# undercarriage.net
KiCad netlist of a schematic drawn in EAGLE
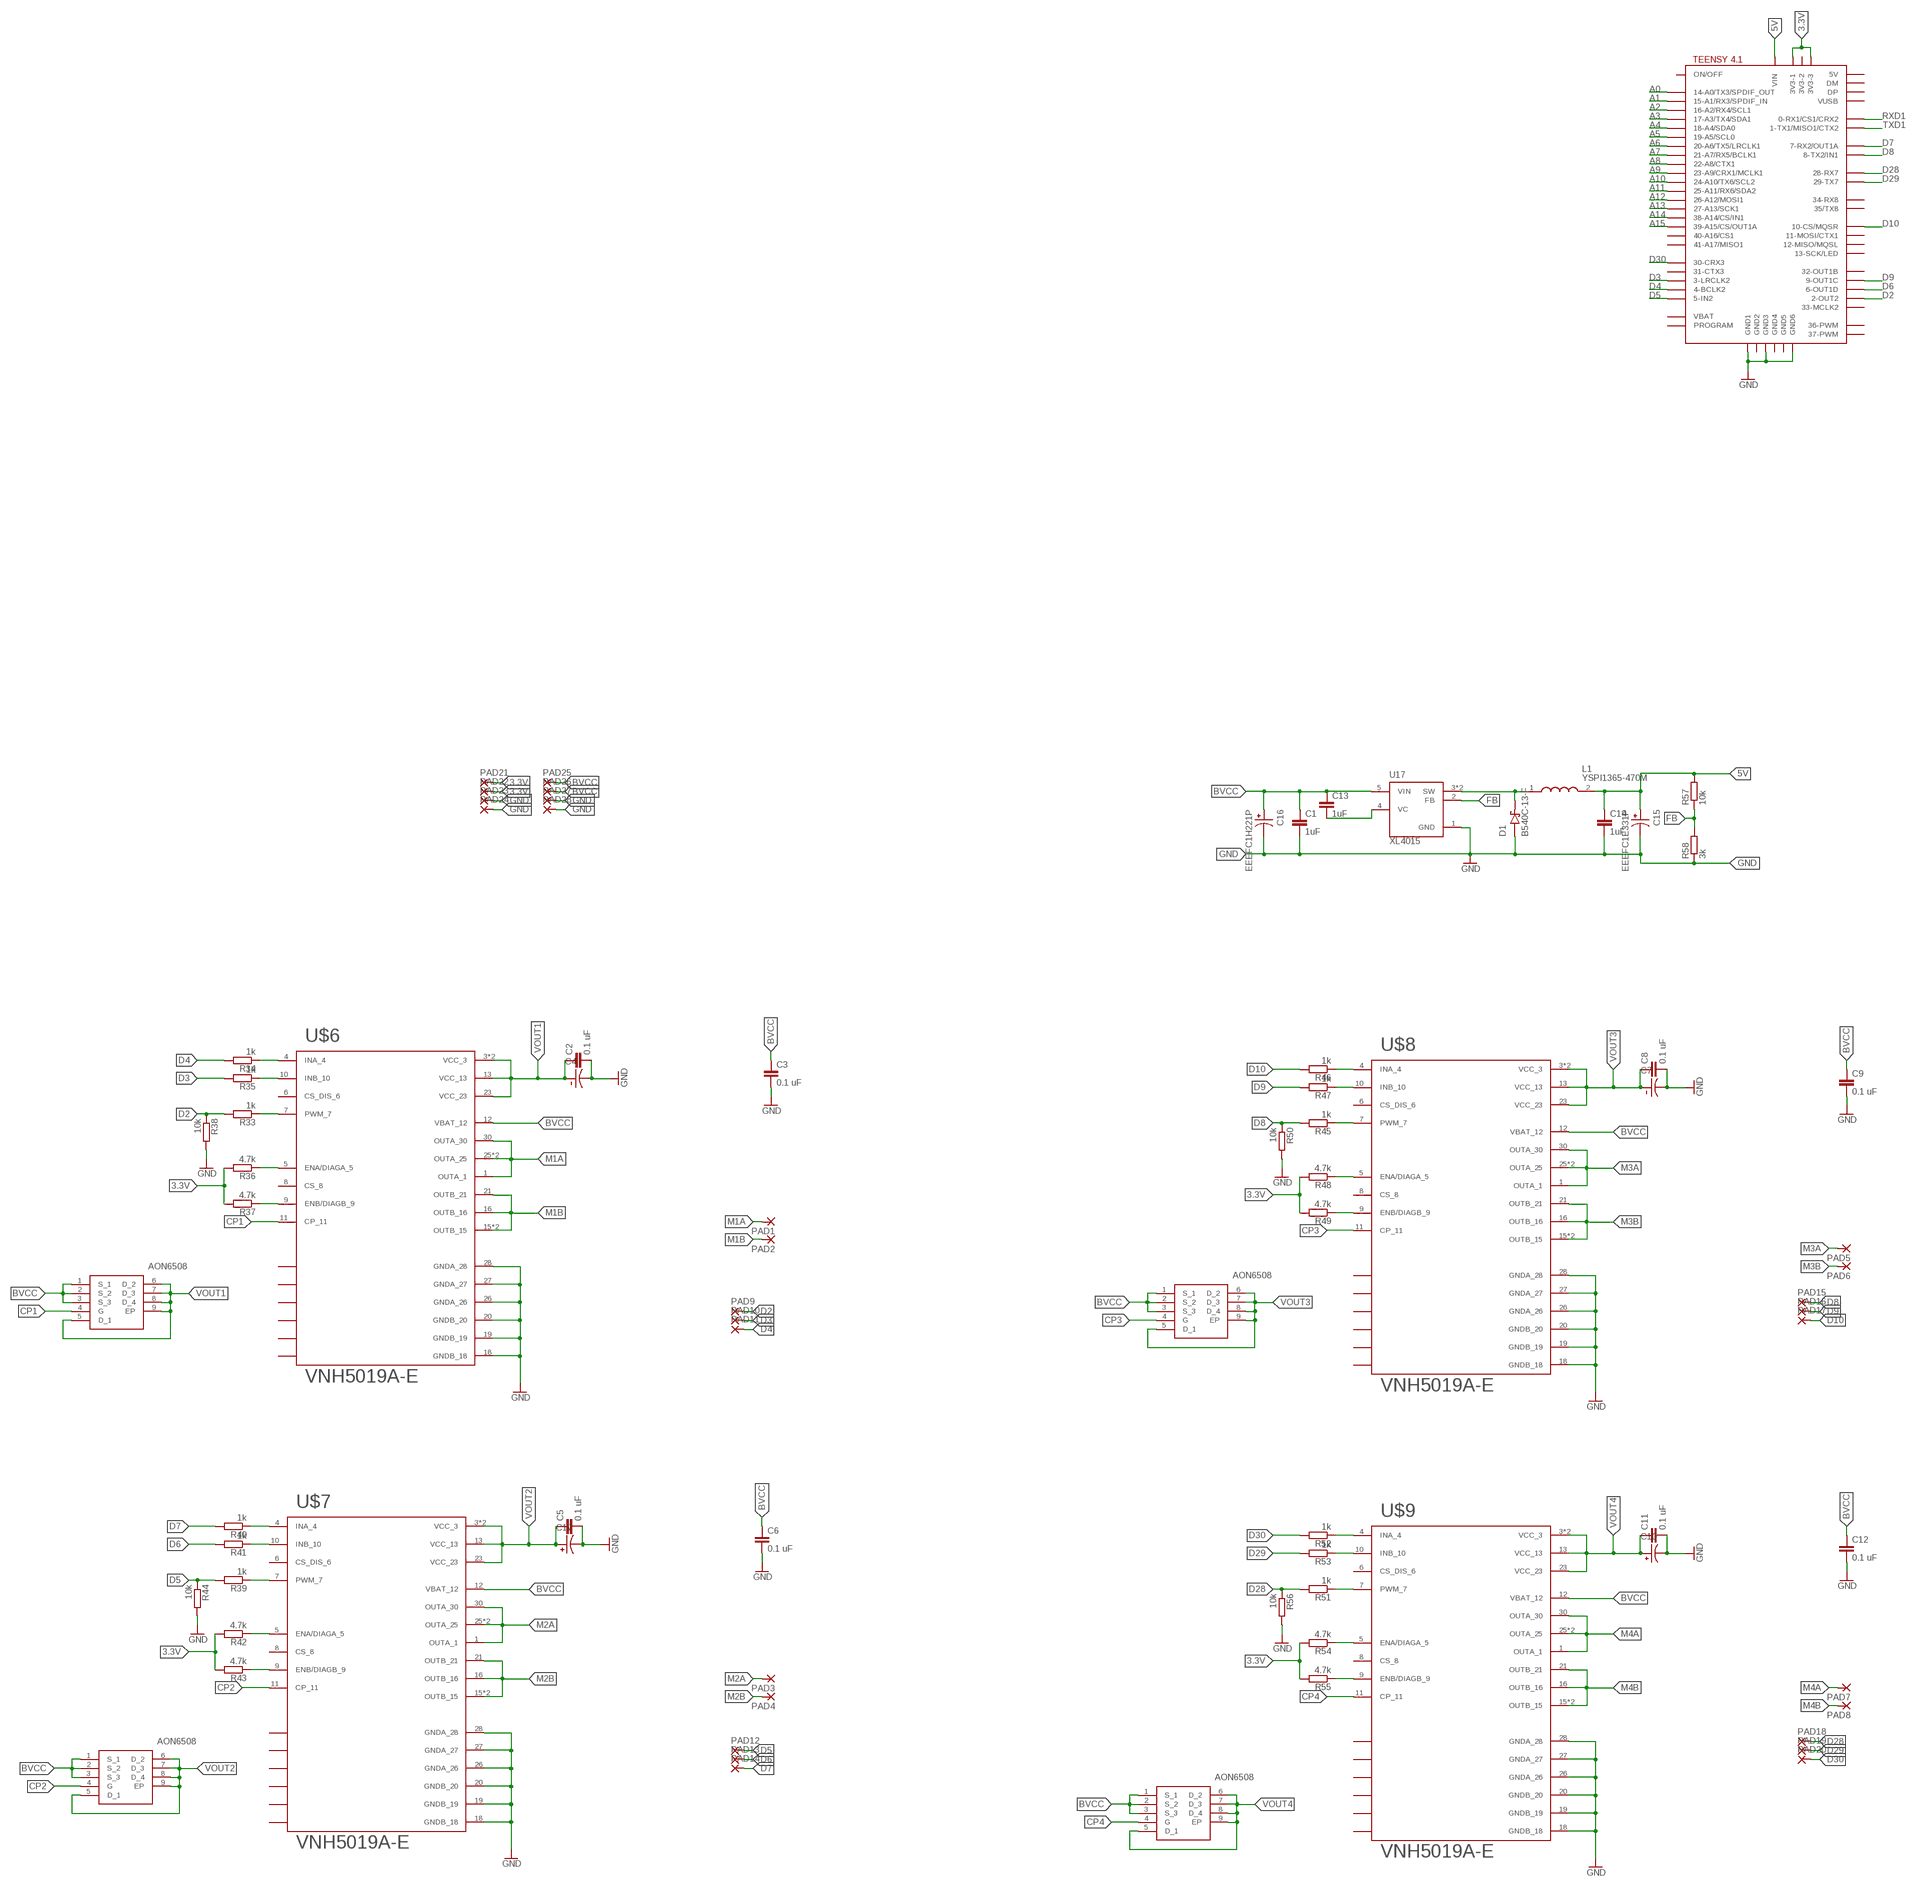
[diagram p0: schematic, sheet 1, part 1 of 2]
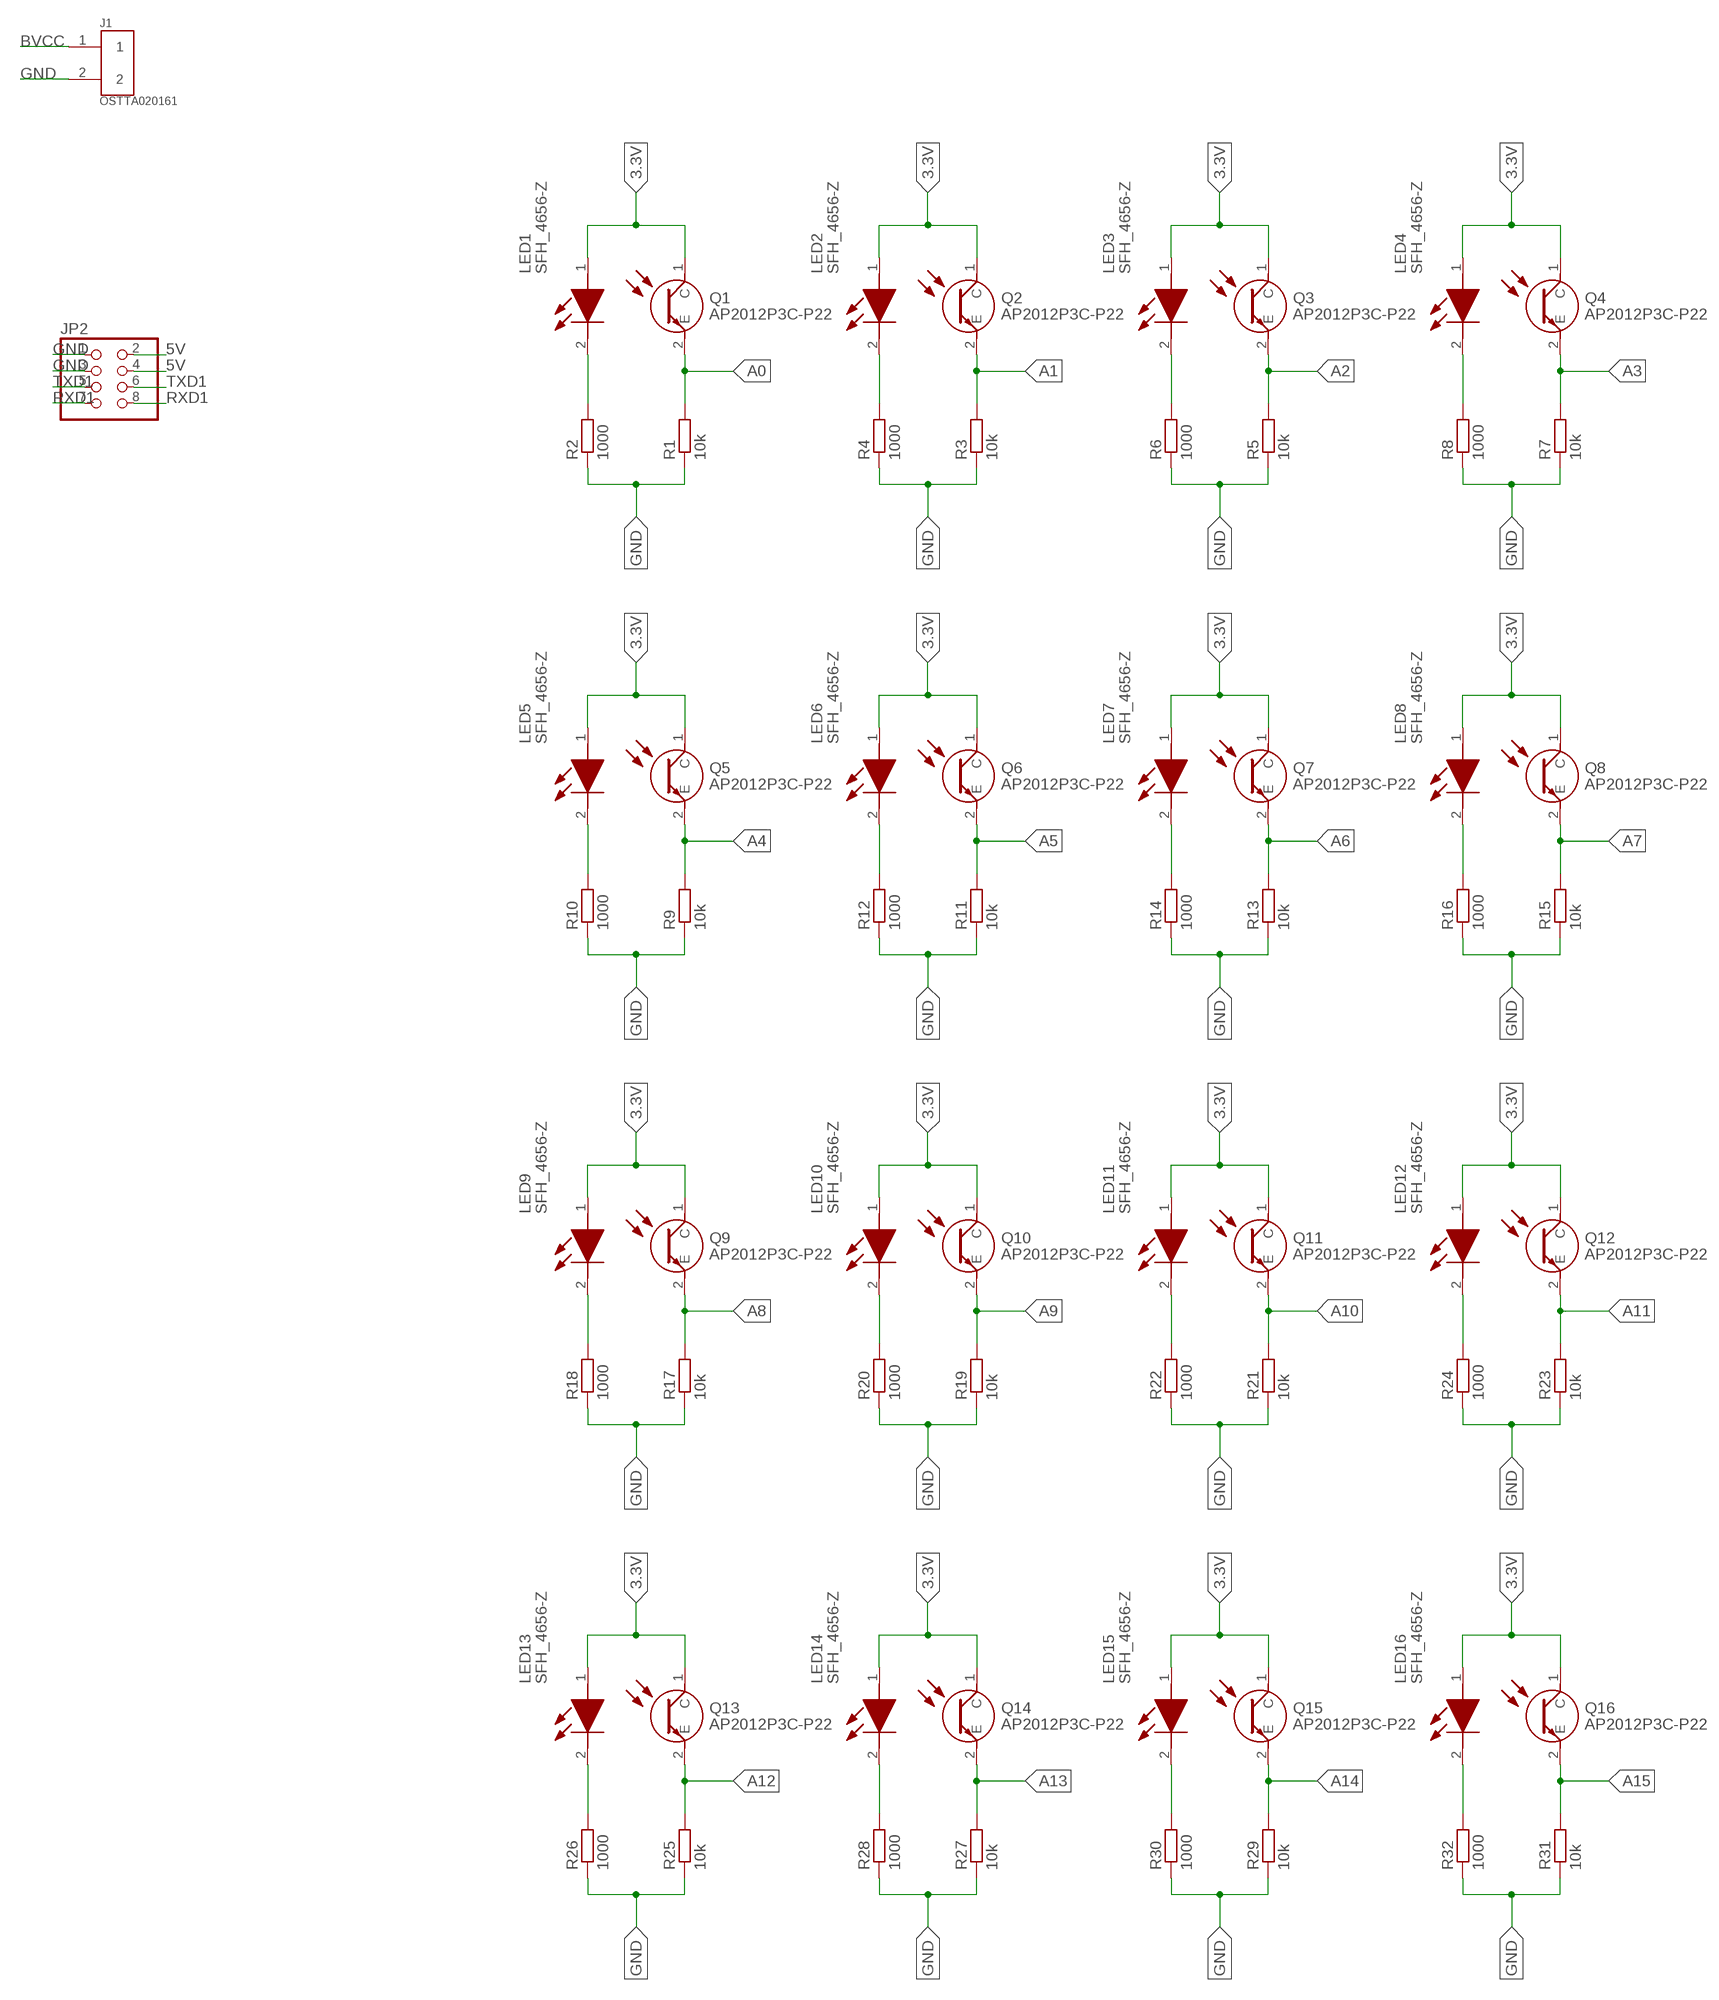
[diagram p1: schematic, sheet 1, part 2 of 2]

(export (version "E")
  (design (tool "Eeschema 10.0.6"))
  (components
    (comp (ref "C1")
      (value "1uF")
      (footprint "eagle-import:C0603")
      (libsource (lib "eagle-import") (part "C-EUC0603"))
    )
    (comp (ref "C2")
      (value "0.1 uF")
      (footprint "eagle-import:C0603")
      (libsource (lib "eagle-import") (part "C-EUC0603"))
    )
    (comp (ref "C3")
      (value "0.1 uF")
      (footprint "eagle-import:C0603")
      (libsource (lib "eagle-import") (part "C-EUC0603"))
    )
    (comp (ref "C4")
      (value "EEEFT1H470AP")
      (footprint "eagle-import:CAP_EEEFT1H470AP")
      (fields (field (name "MF") "Panasonic"))
      (libsource (lib "eagle-import") (part "EEEFT1H470AP"))
    )
    (comp (ref "C5")
      (value "0.1 uF")
      (footprint "eagle-import:C0603")
      (libsource (lib "eagle-import") (part "C-EUC0603"))
    )
    (comp (ref "C6")
      (value "0.1 uF")
      (footprint "eagle-import:C0603")
      (libsource (lib "eagle-import") (part "C-EUC0603"))
    )
    (comp (ref "C7")
      (value "EEEFT1H470AP")
      (footprint "eagle-import:CAP_EEEFT1H470AP")
      (fields (field (name "MF") "Panasonic"))
      (libsource (lib "eagle-import") (part "EEEFT1H470AP"))
    )
    (comp (ref "C8")
      (value "0.1 uF")
      (footprint "eagle-import:C0603")
      (libsource (lib "eagle-import") (part "C-EUC0603"))
    )
    (comp (ref "C9")
      (value "0.1 uF")
      (footprint "eagle-import:C0603")
      (libsource (lib "eagle-import") (part "C-EUC0603"))
    )
    (comp (ref "C10")
      (value "EEEFT1H470AP")
      (footprint "eagle-import:CAP_EEEFT1H470AP")
      (fields (field (name "MF") "Panasonic"))
      (libsource (lib "eagle-import") (part "EEEFT1H470AP"))
    )
    (comp (ref "C11")
      (value "0.1 uF")
      (footprint "eagle-import:C0603")
      (libsource (lib "eagle-import") (part "C-EUC0603"))
    )
    (comp (ref "C12")
      (value "0.1 uF")
      (footprint "eagle-import:C0603")
      (libsource (lib "eagle-import") (part "C-EUC0603"))
    )
    (comp (ref "C13")
      (value "1uF")
      (footprint "eagle-import:C0603")
      (libsource (lib "eagle-import") (part "C-EUC0603"))
    )
    (comp (ref "C14")
      (value "1uF")
      (footprint "eagle-import:C0603")
      (libsource (lib "eagle-import") (part "C-EUC0603"))
    )
    (comp (ref "C15")
      (value "EEEFC1E331P")
      (footprint "eagle-import:CAP_EEEFC1E331P")
      (fields (field (name "MF") "Panasonic"))
      (libsource (lib "eagle-import") (part "EEEFC1E331P"))
    )
    (comp (ref "C16")
      (value "EEEFC1H221P")
      (footprint "eagle-import:CAP_EEEFC1H221P")
      (fields (field (name "MF") "Panasonic"))
      (libsource (lib "eagle-import") (part "EEEFC1H221P"))
    )
    (comp (ref "C17")
      (value "EEEFT1H470AP")
      (footprint "eagle-import:CAP_EEEFT1H470AP")
      (fields (field (name "MF") "Panasonic"))
      (libsource (lib "eagle-import") (part "EEEFT1H470AP"))
    )
    (comp (ref "D1")
      (value "B540C-13-F")
      (footprint "eagle-import:DIOM6959X245N")
      (fields (field (name "MF") "Diodes Inc."))
      (libsource (lib "eagle-import") (part "B540C-13-F"))
    )
    (comp (ref "J1")
      (value "OSTTA020161")
      (footprint "eagle-import:OST_OSTTA020161")
      (fields (field (name "MF") "On Shore"))
      (libsource (lib "eagle-import") (part "OSTTA020161"))
    )
    (comp (ref "JP2")
      (value "PINHD-2X4")
      (footprint "eagle-import:2X04")
      (libsource (lib "eagle-import") (part "PINHD-2X4"))
    )
    (comp (ref "L1")
      (value "YSPI1365-470M")
      (footprint "eagle-import:INDPM138126X650N")
      (libsource (lib "eagle-import") (part "YSPI1365-470M"))
    )
    (comp (ref "LED1")
      (value "SFH_4656-Z")
      (footprint "eagle-import:SFH4656Z")
      (fields
        (field (name "MANUFACTURER_PART_NUMBER") "SFH 4656-Z")
        (field (name "MOUSER_PART_NUMBER") "720-SFH4656-Z")
      )
      (libsource (lib "eagle-import") (part "SFH_4656-Z"))
    )
    (comp (ref "LED2")
      (value "SFH_4656-Z")
      (footprint "eagle-import:SFH4656Z")
      (fields
        (field (name "MANUFACTURER_PART_NUMBER") "SFH 4656-Z")
        (field (name "MOUSER_PART_NUMBER") "720-SFH4656-Z")
      )
      (libsource (lib "eagle-import") (part "SFH_4656-Z"))
    )
    (comp (ref "LED3")
      (value "SFH_4656-Z")
      (footprint "eagle-import:SFH4656Z")
      (fields
        (field (name "MANUFACTURER_PART_NUMBER") "SFH 4656-Z")
        (field (name "MOUSER_PART_NUMBER") "720-SFH4656-Z")
      )
      (libsource (lib "eagle-import") (part "SFH_4656-Z"))
    )
    (comp (ref "LED4")
      (value "SFH_4656-Z")
      (footprint "eagle-import:SFH4656Z")
      (fields
        (field (name "MANUFACTURER_PART_NUMBER") "SFH 4656-Z")
        (field (name "MOUSER_PART_NUMBER") "720-SFH4656-Z")
      )
      (libsource (lib "eagle-import") (part "SFH_4656-Z"))
    )
    (comp (ref "LED5")
      (value "SFH_4656-Z")
      (footprint "eagle-import:SFH4656Z")
      (fields
        (field (name "MANUFACTURER_PART_NUMBER") "SFH 4656-Z")
        (field (name "MOUSER_PART_NUMBER") "720-SFH4656-Z")
      )
      (libsource (lib "eagle-import") (part "SFH_4656-Z"))
    )
    (comp (ref "LED6")
      (value "SFH_4656-Z")
      (footprint "eagle-import:SFH4656Z")
      (fields
        (field (name "MANUFACTURER_PART_NUMBER") "SFH 4656-Z")
        (field (name "MOUSER_PART_NUMBER") "720-SFH4656-Z")
      )
      (libsource (lib "eagle-import") (part "SFH_4656-Z"))
    )
    (comp (ref "LED7")
      (value "SFH_4656-Z")
      (footprint "eagle-import:SFH4656Z")
      (fields
        (field (name "MANUFACTURER_PART_NUMBER") "SFH 4656-Z")
        (field (name "MOUSER_PART_NUMBER") "720-SFH4656-Z")
      )
      (libsource (lib "eagle-import") (part "SFH_4656-Z"))
    )
    (comp (ref "LED8")
      (value "SFH_4656-Z")
      (footprint "eagle-import:SFH4656Z")
      (fields
        (field (name "MANUFACTURER_PART_NUMBER") "SFH 4656-Z")
        (field (name "MOUSER_PART_NUMBER") "720-SFH4656-Z")
      )
      (libsource (lib "eagle-import") (part "SFH_4656-Z"))
    )
    (comp (ref "LED9")
      (value "SFH_4656-Z")
      (footprint "eagle-import:SFH4656Z")
      (fields
        (field (name "MANUFACTURER_PART_NUMBER") "SFH 4656-Z")
        (field (name "MOUSER_PART_NUMBER") "720-SFH4656-Z")
      )
      (libsource (lib "eagle-import") (part "SFH_4656-Z"))
    )
    (comp (ref "LED10")
      (value "SFH_4656-Z")
      (footprint "eagle-import:SFH4656Z")
      (fields
        (field (name "MANUFACTURER_PART_NUMBER") "SFH 4656-Z")
        (field (name "MOUSER_PART_NUMBER") "720-SFH4656-Z")
      )
      (libsource (lib "eagle-import") (part "SFH_4656-Z"))
    )
    (comp (ref "LED11")
      (value "SFH_4656-Z")
      (footprint "eagle-import:SFH4656Z")
      (fields
        (field (name "MANUFACTURER_PART_NUMBER") "SFH 4656-Z")
        (field (name "MOUSER_PART_NUMBER") "720-SFH4656-Z")
      )
      (libsource (lib "eagle-import") (part "SFH_4656-Z"))
    )
    (comp (ref "LED12")
      (value "SFH_4656-Z")
      (footprint "eagle-import:SFH4656Z")
      (fields
        (field (name "MANUFACTURER_PART_NUMBER") "SFH 4656-Z")
        (field (name "MOUSER_PART_NUMBER") "720-SFH4656-Z")
      )
      (libsource (lib "eagle-import") (part "SFH_4656-Z"))
    )
    (comp (ref "LED13")
      (value "SFH_4656-Z")
      (footprint "eagle-import:SFH4656Z")
      (fields
        (field (name "MANUFACTURER_PART_NUMBER") "SFH 4656-Z")
        (field (name "MOUSER_PART_NUMBER") "720-SFH4656-Z")
      )
      (libsource (lib "eagle-import") (part "SFH_4656-Z"))
    )
    (comp (ref "LED14")
      (value "SFH_4656-Z")
      (footprint "eagle-import:SFH4656Z")
      (fields
        (field (name "MANUFACTURER_PART_NUMBER") "SFH 4656-Z")
        (field (name "MOUSER_PART_NUMBER") "720-SFH4656-Z")
      )
      (libsource (lib "eagle-import") (part "SFH_4656-Z"))
    )
    (comp (ref "LED15")
      (value "SFH_4656-Z")
      (footprint "eagle-import:SFH4656Z")
      (fields
        (field (name "MANUFACTURER_PART_NUMBER") "SFH 4656-Z")
        (field (name "MOUSER_PART_NUMBER") "720-SFH4656-Z")
      )
      (libsource (lib "eagle-import") (part "SFH_4656-Z"))
    )
    (comp (ref "LED16")
      (value "SFH_4656-Z")
      (footprint "eagle-import:SFH4656Z")
      (fields
        (field (name "MANUFACTURER_PART_NUMBER") "SFH 4656-Z")
        (field (name "MOUSER_PART_NUMBER") "720-SFH4656-Z")
      )
      (libsource (lib "eagle-import") (part "SFH_4656-Z"))
    )
    (comp (ref "PAD1")
      (value "3,81/1,4")
      (footprint "eagle-import:3,81_1,4")
      (libsource (lib "eagle-import") (part "3,81/1,4"))
    )
    (comp (ref "PAD2")
      (value "3,81/1,4")
      (footprint "eagle-import:3,81_1,4")
      (libsource (lib "eagle-import") (part "3,81/1,4"))
    )
    (comp (ref "PAD3")
      (value "3,81/1,4")
      (footprint "eagle-import:3,81_1,4")
      (libsource (lib "eagle-import") (part "3,81/1,4"))
    )
    (comp (ref "PAD4")
      (value "3,81/1,4")
      (footprint "eagle-import:3,81_1,4")
      (libsource (lib "eagle-import") (part "3,81/1,4"))
    )
    (comp (ref "PAD5")
      (value "3,81/1,4")
      (footprint "eagle-import:3,81_1,4")
      (libsource (lib "eagle-import") (part "3,81/1,4"))
    )
    (comp (ref "PAD6")
      (value "3,81/1,4")
      (footprint "eagle-import:3,81_1,4")
      (libsource (lib "eagle-import") (part "3,81/1,4"))
    )
    (comp (ref "PAD7")
      (value "3,81/1,4")
      (footprint "eagle-import:3,81_1,4")
      (libsource (lib "eagle-import") (part "3,81/1,4"))
    )
    (comp (ref "PAD8")
      (value "3,81/1,4")
      (footprint "eagle-import:3,81_1,4")
      (libsource (lib "eagle-import") (part "3,81/1,4"))
    )
    (comp (ref "PAD9")
      (value "1,6/0,9")
      (footprint "eagle-import:1,6_0,9")
      (libsource (lib "eagle-import") (part "1,6/0,9"))
    )
    (comp (ref "PAD10")
      (value "1,6/0,9")
      (footprint "eagle-import:1,6_0,9")
      (libsource (lib "eagle-import") (part "1,6/0,9"))
    )
    (comp (ref "PAD11")
      (value "1,6/0,9")
      (footprint "eagle-import:1,6_0,9")
      (libsource (lib "eagle-import") (part "1,6/0,9"))
    )
    (comp (ref "PAD12")
      (value "1,6/0,9")
      (footprint "eagle-import:1,6_0,9")
      (libsource (lib "eagle-import") (part "1,6/0,9"))
    )
    (comp (ref "PAD13")
      (value "1,6/0,9")
      (footprint "eagle-import:1,6_0,9")
      (libsource (lib "eagle-import") (part "1,6/0,9"))
    )
    (comp (ref "PAD14")
      (value "1,6/0,9")
      (footprint "eagle-import:1,6_0,9")
      (libsource (lib "eagle-import") (part "1,6/0,9"))
    )
    (comp (ref "PAD15")
      (value "1,6/0,9")
      (footprint "eagle-import:1,6_0,9")
      (libsource (lib "eagle-import") (part "1,6/0,9"))
    )
    (comp (ref "PAD16")
      (value "1,6/0,9")
      (footprint "eagle-import:1,6_0,9")
      (libsource (lib "eagle-import") (part "1,6/0,9"))
    )
    (comp (ref "PAD17")
      (value "1,6/0,9")
      (footprint "eagle-import:1,6_0,9")
      (libsource (lib "eagle-import") (part "1,6/0,9"))
    )
    (comp (ref "PAD18")
      (value "1,6/0,9")
      (footprint "eagle-import:1,6_0,9")
      (libsource (lib "eagle-import") (part "1,6/0,9"))
    )
    (comp (ref "PAD19")
      (value "1,6/0,9")
      (footprint "eagle-import:1,6_0,9")
      (libsource (lib "eagle-import") (part "1,6/0,9"))
    )
    (comp (ref "PAD20")
      (value "1,6/0,9")
      (footprint "eagle-import:1,6_0,9")
      (libsource (lib "eagle-import") (part "1,6/0,9"))
    )
    (comp (ref "PAD21")
      (value "1,6/0,9")
      (footprint "eagle-import:1,6_0,9")
      (libsource (lib "eagle-import") (part "1,6/0,9"))
    )
    (comp (ref "PAD22")
      (value "1,6/0,9")
      (footprint "eagle-import:1,6_0,9")
      (libsource (lib "eagle-import") (part "1,6/0,9"))
    )
    (comp (ref "PAD23")
      (value "1,6/0,9")
      (footprint "eagle-import:1,6_0,9")
      (libsource (lib "eagle-import") (part "1,6/0,9"))
    )
    (comp (ref "PAD24")
      (value "1,6/0,9")
      (footprint "eagle-import:1,6_0,9")
      (libsource (lib "eagle-import") (part "1,6/0,9"))
    )
    (comp (ref "PAD25")
      (value "2,15/1,0")
      (footprint "eagle-import:2,15_1,0")
      (libsource (lib "eagle-import") (part "2,15/1,0"))
    )
    (comp (ref "PAD26")
      (value "2,15/1,0")
      (footprint "eagle-import:2,15_1,0")
      (libsource (lib "eagle-import") (part "2,15/1,0"))
    )
    (comp (ref "PAD27")
      (value "2,15/1,0")
      (footprint "eagle-import:2,15_1,0")
      (libsource (lib "eagle-import") (part "2,15/1,0"))
    )
    (comp (ref "PAD28")
      (value "2,15/1,0")
      (footprint "eagle-import:2,15_1,0")
      (libsource (lib "eagle-import") (part "2,15/1,0"))
    )
    (comp (ref "Q1")
      (value "AP2012P3C-P22")
      (footprint "eagle-import:AP2012P3CP22")
      (fields (field (name "MOUSER_PART_NUMBER") "604-AP2012P3C-P22"))
      (libsource (lib "eagle-import") (part "AP2012P3C-P22"))
    )
    (comp (ref "Q2")
      (value "AP2012P3C-P22")
      (footprint "eagle-import:AP2012P3CP22")
      (fields (field (name "MOUSER_PART_NUMBER") "604-AP2012P3C-P22"))
      (libsource (lib "eagle-import") (part "AP2012P3C-P22"))
    )
    (comp (ref "Q3")
      (value "AP2012P3C-P22")
      (footprint "eagle-import:AP2012P3CP22")
      (fields (field (name "MOUSER_PART_NUMBER") "604-AP2012P3C-P22"))
      (libsource (lib "eagle-import") (part "AP2012P3C-P22"))
    )
    (comp (ref "Q4")
      (value "AP2012P3C-P22")
      (footprint "eagle-import:AP2012P3CP22")
      (fields (field (name "MOUSER_PART_NUMBER") "604-AP2012P3C-P22"))
      (libsource (lib "eagle-import") (part "AP2012P3C-P22"))
    )
    (comp (ref "Q5")
      (value "AP2012P3C-P22")
      (footprint "eagle-import:AP2012P3CP22")
      (fields (field (name "MOUSER_PART_NUMBER") "604-AP2012P3C-P22"))
      (libsource (lib "eagle-import") (part "AP2012P3C-P22"))
    )
    (comp (ref "Q6")
      (value "AP2012P3C-P22")
      (footprint "eagle-import:AP2012P3CP22")
      (fields (field (name "MOUSER_PART_NUMBER") "604-AP2012P3C-P22"))
      (libsource (lib "eagle-import") (part "AP2012P3C-P22"))
    )
    (comp (ref "Q7")
      (value "AP2012P3C-P22")
      (footprint "eagle-import:AP2012P3CP22")
      (fields (field (name "MOUSER_PART_NUMBER") "604-AP2012P3C-P22"))
      (libsource (lib "eagle-import") (part "AP2012P3C-P22"))
    )
    (comp (ref "Q8")
      (value "AP2012P3C-P22")
      (footprint "eagle-import:AP2012P3CP22")
      (fields (field (name "MOUSER_PART_NUMBER") "604-AP2012P3C-P22"))
      (libsource (lib "eagle-import") (part "AP2012P3C-P22"))
    )
    (comp (ref "Q9")
      (value "AP2012P3C-P22")
      (footprint "eagle-import:AP2012P3CP22")
      (fields (field (name "MOUSER_PART_NUMBER") "604-AP2012P3C-P22"))
      (libsource (lib "eagle-import") (part "AP2012P3C-P22"))
    )
    (comp (ref "Q10")
      (value "AP2012P3C-P22")
      (footprint "eagle-import:AP2012P3CP22")
      (fields (field (name "MOUSER_PART_NUMBER") "604-AP2012P3C-P22"))
      (libsource (lib "eagle-import") (part "AP2012P3C-P22"))
    )
    (comp (ref "Q11")
      (value "AP2012P3C-P22")
      (footprint "eagle-import:AP2012P3CP22")
      (fields (field (name "MOUSER_PART_NUMBER") "604-AP2012P3C-P22"))
      (libsource (lib "eagle-import") (part "AP2012P3C-P22"))
    )
    (comp (ref "Q12")
      (value "AP2012P3C-P22")
      (footprint "eagle-import:AP2012P3CP22")
      (fields (field (name "MOUSER_PART_NUMBER") "604-AP2012P3C-P22"))
      (libsource (lib "eagle-import") (part "AP2012P3C-P22"))
    )
    (comp (ref "Q13")
      (value "AP2012P3C-P22")
      (footprint "eagle-import:AP2012P3CP22")
      (fields (field (name "MOUSER_PART_NUMBER") "604-AP2012P3C-P22"))
      (libsource (lib "eagle-import") (part "AP2012P3C-P22"))
    )
    (comp (ref "Q14")
      (value "AP2012P3C-P22")
      (footprint "eagle-import:AP2012P3CP22")
      (fields (field (name "MOUSER_PART_NUMBER") "604-AP2012P3C-P22"))
      (libsource (lib "eagle-import") (part "AP2012P3C-P22"))
    )
    (comp (ref "Q15")
      (value "AP2012P3C-P22")
      (footprint "eagle-import:AP2012P3CP22")
      (fields (field (name "MOUSER_PART_NUMBER") "604-AP2012P3C-P22"))
      (libsource (lib "eagle-import") (part "AP2012P3C-P22"))
    )
    (comp (ref "Q16")
      (value "AP2012P3C-P22")
      (footprint "eagle-import:AP2012P3CP22")
      (fields (field (name "MOUSER_PART_NUMBER") "604-AP2012P3C-P22"))
      (libsource (lib "eagle-import") (part "AP2012P3C-P22"))
    )
    (comp (ref "Q17")
      (value "AON6508")
      (footprint "eagle-import:AON6508")
      (libsource (lib "eagle-import") (part "AON6508"))
    )
    (comp (ref "Q18")
      (value "AON6508")
      (footprint "eagle-import:AON6508")
      (libsource (lib "eagle-import") (part "AON6508"))
    )
    (comp (ref "Q19")
      (value "AON6508")
      (footprint "eagle-import:AON6508")
      (libsource (lib "eagle-import") (part "AON6508"))
    )
    (comp (ref "Q20")
      (value "AON6508")
      (footprint "eagle-import:AON6508")
      (libsource (lib "eagle-import") (part "AON6508"))
    )
    (comp (ref "R1")
      (value "10k")
      (footprint "eagle-import:R0603")
      (libsource (lib "eagle-import") (part "R-EU_R0603"))
    )
    (comp (ref "R2")
      (value "1000")
      (footprint "eagle-import:R0603")
      (libsource (lib "eagle-import") (part "R-EU_R0603"))
    )
    (comp (ref "R3")
      (value "10k")
      (footprint "eagle-import:R0603")
      (libsource (lib "eagle-import") (part "R-EU_R0603"))
    )
    (comp (ref "R4")
      (value "1000")
      (footprint "eagle-import:R0603")
      (libsource (lib "eagle-import") (part "R-EU_R0603"))
    )
    (comp (ref "R5")
      (value "10k")
      (footprint "eagle-import:R0603")
      (libsource (lib "eagle-import") (part "R-EU_R0603"))
    )
    (comp (ref "R6")
      (value "1000")
      (footprint "eagle-import:R0603")
      (libsource (lib "eagle-import") (part "R-EU_R0603"))
    )
    (comp (ref "R7")
      (value "10k")
      (footprint "eagle-import:R0603")
      (libsource (lib "eagle-import") (part "R-EU_R0603"))
    )
    (comp (ref "R8")
      (value "1000")
      (footprint "eagle-import:R0603")
      (libsource (lib "eagle-import") (part "R-EU_R0603"))
    )
    (comp (ref "R9")
      (value "10k")
      (footprint "eagle-import:R0603")
      (libsource (lib "eagle-import") (part "R-EU_R0603"))
    )
    (comp (ref "R10")
      (value "1000")
      (footprint "eagle-import:R0603")
      (libsource (lib "eagle-import") (part "R-EU_R0603"))
    )
    (comp (ref "R11")
      (value "10k")
      (footprint "eagle-import:R0603")
      (libsource (lib "eagle-import") (part "R-EU_R0603"))
    )
    (comp (ref "R12")
      (value "1000")
      (footprint "eagle-import:R0603")
      (libsource (lib "eagle-import") (part "R-EU_R0603"))
    )
    (comp (ref "R13")
      (value "10k")
      (footprint "eagle-import:R0603")
      (libsource (lib "eagle-import") (part "R-EU_R0603"))
    )
    (comp (ref "R14")
      (value "1000")
      (footprint "eagle-import:R0603")
      (libsource (lib "eagle-import") (part "R-EU_R0603"))
    )
    (comp (ref "R15")
      (value "10k")
      (footprint "eagle-import:R0603")
      (libsource (lib "eagle-import") (part "R-EU_R0603"))
    )
    (comp (ref "R16")
      (value "1000")
      (footprint "eagle-import:R0603")
      (libsource (lib "eagle-import") (part "R-EU_R0603"))
    )
    (comp (ref "R17")
      (value "10k")
      (footprint "eagle-import:R0603")
      (libsource (lib "eagle-import") (part "R-EU_R0603"))
    )
    (comp (ref "R18")
      (value "1000")
      (footprint "eagle-import:R0603")
      (libsource (lib "eagle-import") (part "R-EU_R0603"))
    )
    (comp (ref "R19")
      (value "10k")
      (footprint "eagle-import:R0603")
      (libsource (lib "eagle-import") (part "R-EU_R0603"))
    )
    (comp (ref "R20")
      (value "1000")
      (footprint "eagle-import:R0603")
      (libsource (lib "eagle-import") (part "R-EU_R0603"))
    )
    (comp (ref "R21")
      (value "10k")
      (footprint "eagle-import:R0603")
      (libsource (lib "eagle-import") (part "R-EU_R0603"))
    )
    (comp (ref "R22")
      (value "1000")
      (footprint "eagle-import:R0603")
      (libsource (lib "eagle-import") (part "R-EU_R0603"))
    )
    (comp (ref "R23")
      (value "10k")
      (footprint "eagle-import:R0603")
      (libsource (lib "eagle-import") (part "R-EU_R0603"))
    )
    (comp (ref "R24")
      (value "1000")
      (footprint "eagle-import:R0603")
      (libsource (lib "eagle-import") (part "R-EU_R0603"))
    )
    (comp (ref "R25")
      (value "10k")
      (footprint "eagle-import:R0603")
      (libsource (lib "eagle-import") (part "R-EU_R0603"))
    )
    (comp (ref "R26")
      (value "1000")
      (footprint "eagle-import:R0603")
      (libsource (lib "eagle-import") (part "R-EU_R0603"))
    )
    (comp (ref "R27")
      (value "10k")
      (footprint "eagle-import:R0603")
      (libsource (lib "eagle-import") (part "R-EU_R0603"))
    )
    (comp (ref "R28")
      (value "1000")
      (footprint "eagle-import:R0603")
      (libsource (lib "eagle-import") (part "R-EU_R0603"))
    )
    (comp (ref "R29")
      (value "10k")
      (footprint "eagle-import:R0603")
      (libsource (lib "eagle-import") (part "R-EU_R0603"))
    )
    (comp (ref "R30")
      (value "1000")
      (footprint "eagle-import:R0603")
      (libsource (lib "eagle-import") (part "R-EU_R0603"))
    )
    (comp (ref "R31")
      (value "10k")
      (footprint "eagle-import:R0603")
      (libsource (lib "eagle-import") (part "R-EU_R0603"))
    )
    (comp (ref "R32")
      (value "1000")
      (footprint "eagle-import:R0603")
      (libsource (lib "eagle-import") (part "R-EU_R0603"))
    )
    (comp (ref "R33")
      (value "1k")
      (footprint "eagle-import:R0603")
      (libsource (lib "eagle-import") (part "R-EU_R0603"))
    )
    (comp (ref "R34")
      (value "1k")
      (footprint "eagle-import:R0603")
      (libsource (lib "eagle-import") (part "R-EU_R0603"))
    )
    (comp (ref "R35")
      (value "1k")
      (footprint "eagle-import:R0603")
      (libsource (lib "eagle-import") (part "R-EU_R0603"))
    )
    (comp (ref "R36")
      (value "4.7k")
      (footprint "eagle-import:R0603")
      (libsource (lib "eagle-import") (part "R-EU_R0603"))
    )
    (comp (ref "R37")
      (value "4.7k")
      (footprint "eagle-import:R0603")
      (libsource (lib "eagle-import") (part "R-EU_R0603"))
    )
    (comp (ref "R38")
      (value "10k")
      (footprint "eagle-import:R0603")
      (libsource (lib "eagle-import") (part "R-EU_R0603"))
    )
    (comp (ref "R39")
      (value "1k")
      (footprint "eagle-import:R0603")
      (libsource (lib "eagle-import") (part "R-EU_R0603"))
    )
    (comp (ref "R40")
      (value "1k")
      (footprint "eagle-import:R0603")
      (libsource (lib "eagle-import") (part "R-EU_R0603"))
    )
    (comp (ref "R41")
      (value "1k")
      (footprint "eagle-import:R0603")
      (libsource (lib "eagle-import") (part "R-EU_R0603"))
    )
    (comp (ref "R42")
      (value "4.7k")
      (footprint "eagle-import:R0603")
      (libsource (lib "eagle-import") (part "R-EU_R0603"))
    )
    (comp (ref "R43")
      (value "4.7k")
      (footprint "eagle-import:R0603")
      (libsource (lib "eagle-import") (part "R-EU_R0603"))
    )
    (comp (ref "R44")
      (value "10k")
      (footprint "eagle-import:R0603")
      (libsource (lib "eagle-import") (part "R-EU_R0603"))
    )
    (comp (ref "R45")
      (value "1k")
      (footprint "eagle-import:R0603")
      (libsource (lib "eagle-import") (part "R-EU_R0603"))
    )
    (comp (ref "R46")
      (value "1k")
      (footprint "eagle-import:R0603")
      (libsource (lib "eagle-import") (part "R-EU_R0603"))
    )
    (comp (ref "R47")
      (value "1k")
      (footprint "eagle-import:R0603")
      (libsource (lib "eagle-import") (part "R-EU_R0603"))
    )
    (comp (ref "R48")
      (value "4.7k")
      (footprint "eagle-import:R0603")
      (libsource (lib "eagle-import") (part "R-EU_R0603"))
    )
    (comp (ref "R49")
      (value "4.7k")
      (footprint "eagle-import:R0603")
      (libsource (lib "eagle-import") (part "R-EU_R0603"))
    )
    (comp (ref "R50")
      (value "10k")
      (footprint "eagle-import:R0603")
      (libsource (lib "eagle-import") (part "R-EU_R0603"))
    )
    (comp (ref "R51")
      (value "1k")
      (footprint "eagle-import:R0603")
      (libsource (lib "eagle-import") (part "R-EU_R0603"))
    )
    (comp (ref "R52")
      (value "1k")
      (footprint "eagle-import:R0603")
      (libsource (lib "eagle-import") (part "R-EU_R0603"))
    )
    (comp (ref "R53")
      (value "1k")
      (footprint "eagle-import:R0603")
      (libsource (lib "eagle-import") (part "R-EU_R0603"))
    )
    (comp (ref "R54")
      (value "4.7k")
      (footprint "eagle-import:R0603")
      (libsource (lib "eagle-import") (part "R-EU_R0603"))
    )
    (comp (ref "R55")
      (value "4.7k")
      (footprint "eagle-import:R0603")
      (libsource (lib "eagle-import") (part "R-EU_R0603"))
    )
    (comp (ref "R56")
      (value "10k")
      (footprint "eagle-import:R0603")
      (libsource (lib "eagle-import") (part "R-EU_R0603"))
    )
    (comp (ref "R57")
      (value "10k")
      (footprint "eagle-import:R0603")
      (libsource (lib "eagle-import") (part "R-EU_R0603"))
    )
    (comp (ref "R58")
      (value "3k")
      (footprint "eagle-import:R0603")
      (libsource (lib "eagle-import") (part "R-EU_R0603"))
    )
    (comp (ref "U$5")
      (value "TEENSY41-E")
      (footprint "eagle-import:TENNSY41-E")
      (libsource (lib "eagle-import") (part "TEENSY41-E"))
    )
    (comp (ref "U$6")
      (value "VNH5019A-E")
      (footprint "eagle-import:IC_MULTIPOWERSO-30TR")
      (fields (field (name "MF") "STMicroelectronics"))
      (libsource (lib "eagle-import") (part "VNH5019A-E"))
    )
    (comp (ref "U$7")
      (value "VNH5019A-E")
      (footprint "eagle-import:IC_MULTIPOWERSO-30TR")
      (fields (field (name "MF") "STMicroelectronics"))
      (libsource (lib "eagle-import") (part "VNH5019A-E"))
    )
    (comp (ref "U$8")
      (value "VNH5019A-E")
      (footprint "eagle-import:IC_MULTIPOWERSO-30TR")
      (fields (field (name "MF") "STMicroelectronics"))
      (libsource (lib "eagle-import") (part "VNH5019A-E"))
    )
    (comp (ref "U$9")
      (value "VNH5019A-E")
      (footprint "eagle-import:IC_MULTIPOWERSO-30TR")
      (fields (field (name "MF") "STMicroelectronics"))
      (libsource (lib "eagle-import") (part "VNH5019A-E"))
    )
    (comp (ref "U17")
      (value "XL4015")
      (footprint "eagle-import:CONV_XL4015")
      (fields (field (name "MF") "XLSEMI"))
      (libsource (lib "eagle-import") (part "XL4015"))
    )
  )
  (nets
    (net (code "1") (name "/RXD1") (class "Default")
      (node (ref "JP2") (pin "7") (pinfunction "7_7") (pintype "passive"))
      (node (ref "JP2") (pin "8") (pinfunction "8_8") (pintype "passive"))
      (node (ref "U$5") (pin "0-RX1/CS1/CRX2") (pinfunction "0-RX1/CS1/CRX2_0-RX1/CS1/CRX2") (pintype "bidirectional"))
    )
    (net (code "2") (name "/TXD1") (class "Default")
      (node (ref "JP2") (pin "5") (pinfunction "5_5") (pintype "passive"))
      (node (ref "JP2") (pin "6") (pinfunction "6_6") (pintype "passive"))
      (node (ref "U$5") (pin "1-TX1/MISO1/CTX2") (pinfunction "1-TX1/MISO1/CTX2_1-TX1/MISO1/CTX2") (pintype "bidirectional"))
    )
    (net (code "3") (name "3.3V") (class "Default")
      (node (ref "LED1") (pin "1") (pinfunction "A_1") (pintype "bidirectional"))
      (node (ref "LED10") (pin "1") (pinfunction "A_1") (pintype "bidirectional"))
      (node (ref "LED11") (pin "1") (pinfunction "A_1") (pintype "bidirectional"))
      (node (ref "LED12") (pin "1") (pinfunction "A_1") (pintype "bidirectional"))
      (node (ref "LED13") (pin "1") (pinfunction "A_1") (pintype "bidirectional"))
      (node (ref "LED14") (pin "1") (pinfunction "A_1") (pintype "bidirectional"))
      (node (ref "LED15") (pin "1") (pinfunction "A_1") (pintype "bidirectional"))
      (node (ref "LED16") (pin "1") (pinfunction "A_1") (pintype "bidirectional"))
      (node (ref "LED2") (pin "1") (pinfunction "A_1") (pintype "bidirectional"))
      (node (ref "LED3") (pin "1") (pinfunction "A_1") (pintype "bidirectional"))
      (node (ref "LED4") (pin "1") (pinfunction "A_1") (pintype "bidirectional"))
      (node (ref "LED5") (pin "1") (pinfunction "A_1") (pintype "bidirectional"))
      (node (ref "LED6") (pin "1") (pinfunction "A_1") (pintype "bidirectional"))
      (node (ref "LED7") (pin "1") (pinfunction "A_1") (pintype "bidirectional"))
      (node (ref "LED8") (pin "1") (pinfunction "A_1") (pintype "bidirectional"))
      (node (ref "LED9") (pin "1") (pinfunction "A_1") (pintype "bidirectional"))
      (node (ref "PAD21") (pin "1") (pinfunction "P_1") (pintype "passive"))
      (node (ref "PAD22") (pin "1") (pinfunction "P_1") (pintype "passive"))
      (node (ref "Q1") (pin "1") (pinfunction "C_1") (pintype "bidirectional"))
      (node (ref "Q10") (pin "1") (pinfunction "C_1") (pintype "bidirectional"))
      (node (ref "Q11") (pin "1") (pinfunction "C_1") (pintype "bidirectional"))
      (node (ref "Q12") (pin "1") (pinfunction "C_1") (pintype "bidirectional"))
      (node (ref "Q13") (pin "1") (pinfunction "C_1") (pintype "bidirectional"))
      (node (ref "Q14") (pin "1") (pinfunction "C_1") (pintype "bidirectional"))
      (node (ref "Q15") (pin "1") (pinfunction "C_1") (pintype "bidirectional"))
      (node (ref "Q16") (pin "1") (pinfunction "C_1") (pintype "bidirectional"))
      (node (ref "Q2") (pin "1") (pinfunction "C_1") (pintype "bidirectional"))
      (node (ref "Q3") (pin "1") (pinfunction "C_1") (pintype "bidirectional"))
      (node (ref "Q4") (pin "1") (pinfunction "C_1") (pintype "bidirectional"))
      (node (ref "Q5") (pin "1") (pinfunction "C_1") (pintype "bidirectional"))
      (node (ref "Q6") (pin "1") (pinfunction "C_1") (pintype "bidirectional"))
      (node (ref "Q7") (pin "1") (pinfunction "C_1") (pintype "bidirectional"))
      (node (ref "Q8") (pin "1") (pinfunction "C_1") (pintype "bidirectional"))
      (node (ref "Q9") (pin "1") (pinfunction "C_1") (pintype "bidirectional"))
      (node (ref "R36") (pin "2") (pinfunction "2_2") (pintype "passive"))
      (node (ref "R37") (pin "2") (pinfunction "2_2") (pintype "passive"))
      (node (ref "R42") (pin "2") (pinfunction "2_2") (pintype "passive"))
      (node (ref "R43") (pin "2") (pinfunction "2_2") (pintype "passive"))
      (node (ref "R48") (pin "2") (pinfunction "2_2") (pintype "passive"))
      (node (ref "R49") (pin "2") (pinfunction "2_2") (pintype "passive"))
      (node (ref "R54") (pin "2") (pinfunction "2_2") (pintype "passive"))
      (node (ref "R55") (pin "2") (pinfunction "2_2") (pintype "passive"))
      (node (ref "U$5") (pin "3V3-1") (pinfunction "3V3-1_3V3-1") (pintype "bidirectional"))
      (node (ref "U$5") (pin "3V3-3") (pinfunction "3V3-3_3V3-3") (pintype "bidirectional"))
    )
    (net (code "4") (name "5V") (class "Default")
      (node (ref "C14") (pin "1") (pinfunction "1_1") (pintype "passive"))
      (node (ref "C15") (pin "1") (pinfunction "1_1") (pintype "passive"))
      (node (ref "JP2") (pin "2") (pinfunction "2_2") (pintype "passive"))
      (node (ref "JP2") (pin "4") (pinfunction "4_4") (pintype "passive"))
      (node (ref "L1") (pin "2") (pinfunction "2_2") (pintype "bidirectional"))
      (node (ref "R57") (pin "2") (pinfunction "2_2") (pintype "passive"))
      (node (ref "U$5") (pin "VIN") (pinfunction "VIN_VIN") (pintype "bidirectional"))
    )
    (net (code "5") (name "A0") (class "Default")
      (node (ref "Q1") (pin "2") (pinfunction "E_2") (pintype "bidirectional"))
      (node (ref "R1") (pin "2") (pinfunction "2_2") (pintype "passive"))
      (node (ref "U$5") (pin "14-A0/TX3/SPDIF_OUT") (pinfunction "14-A0/TX3/SPDIF_OUT_14-A0/TX3/SPDIF_OUT") (pintype "bidirectional"))
    )
    (net (code "6") (name "A1") (class "Default")
      (node (ref "Q2") (pin "2") (pinfunction "E_2") (pintype "bidirectional"))
      (node (ref "R3") (pin "2") (pinfunction "2_2") (pintype "passive"))
      (node (ref "U$5") (pin "15-A1/RX3/SPDIF_IN") (pinfunction "15-A1/RX3/SPDIF_IN_15-A1/RX3/SPDIF_IN") (pintype "bidirectional"))
    )
    (net (code "7") (name "A2") (class "Default")
      (node (ref "Q3") (pin "2") (pinfunction "E_2") (pintype "bidirectional"))
      (node (ref "R5") (pin "2") (pinfunction "2_2") (pintype "passive"))
      (node (ref "U$5") (pin "16-A2/RX4/SCL1") (pinfunction "16-A2/RX4/SCL1_16-A2/RX4/SCL1") (pintype "bidirectional"))
    )
    (net (code "8") (name "A3") (class "Default")
      (node (ref "Q4") (pin "2") (pinfunction "E_2") (pintype "bidirectional"))
      (node (ref "R7") (pin "2") (pinfunction "2_2") (pintype "passive"))
      (node (ref "U$5") (pin "17-A3/TX4/SDA1") (pinfunction "17-A3/TX4/SDA1_17-A3/TX4/SDA1") (pintype "bidirectional"))
    )
    (net (code "9") (name "A4") (class "Default")
      (node (ref "Q5") (pin "2") (pinfunction "E_2") (pintype "bidirectional"))
      (node (ref "R9") (pin "2") (pinfunction "2_2") (pintype "passive"))
      (node (ref "U$5") (pin "18-A4/SDA0") (pinfunction "18-A4/SDA0_18-A4/SDA0") (pintype "bidirectional"))
    )
    (net (code "10") (name "A5") (class "Default")
      (node (ref "Q6") (pin "2") (pinfunction "E_2") (pintype "bidirectional"))
      (node (ref "R11") (pin "2") (pinfunction "2_2") (pintype "passive"))
      (node (ref "U$5") (pin "19-A5/SCL0") (pinfunction "19-A5/SCL0_19-A5/SCL0") (pintype "bidirectional"))
    )
    (net (code "11") (name "A6") (class "Default")
      (node (ref "Q7") (pin "2") (pinfunction "E_2") (pintype "bidirectional"))
      (node (ref "R13") (pin "2") (pinfunction "2_2") (pintype "passive"))
      (node (ref "U$5") (pin "20-A6/TX5/LRCLK1") (pinfunction "20-A6/TX5/LRCLK1_20-A6/TX5/LRCLK1") (pintype "bidirectional"))
    )
    (net (code "12") (name "A7") (class "Default")
      (node (ref "Q8") (pin "2") (pinfunction "E_2") (pintype "bidirectional"))
      (node (ref "R15") (pin "2") (pinfunction "2_2") (pintype "passive"))
      (node (ref "U$5") (pin "21-A7/RX5/BCLK1") (pinfunction "21-A7/RX5/BCLK1_21-A7/RX5/BCLK1") (pintype "bidirectional"))
    )
    (net (code "13") (name "A8") (class "Default")
      (node (ref "Q9") (pin "2") (pinfunction "E_2") (pintype "bidirectional"))
      (node (ref "R17") (pin "2") (pinfunction "2_2") (pintype "passive"))
      (node (ref "U$5") (pin "22-A8/CTX1") (pinfunction "22-A8/CTX1_22-A8/CTX1") (pintype "bidirectional"))
    )
    (net (code "14") (name "A9") (class "Default")
      (node (ref "Q10") (pin "2") (pinfunction "E_2") (pintype "bidirectional"))
      (node (ref "R19") (pin "2") (pinfunction "2_2") (pintype "passive"))
      (node (ref "U$5") (pin "23-A9/CRX1/MCLK1") (pinfunction "23-A9/CRX1/MCLK1_23-A9/CRX1/MCLK1") (pintype "bidirectional"))
    )
    (net (code "15") (name "A10") (class "Default")
      (node (ref "Q11") (pin "2") (pinfunction "E_2") (pintype "bidirectional"))
      (node (ref "R21") (pin "2") (pinfunction "2_2") (pintype "passive"))
      (node (ref "U$5") (pin "24-A10/TX6/SCL2") (pinfunction "24-A10/TX6/SCL2_24-A10/TX6/SCL2") (pintype "bidirectional"))
    )
    (net (code "16") (name "A11") (class "Default")
      (node (ref "Q12") (pin "2") (pinfunction "E_2") (pintype "bidirectional"))
      (node (ref "R23") (pin "2") (pinfunction "2_2") (pintype "passive"))
      (node (ref "U$5") (pin "25-A11/RX6/SDA2") (pinfunction "25-A11/RX6/SDA2_25-A11/RX6/SDA2") (pintype "bidirectional"))
    )
    (net (code "17") (name "A12") (class "Default")
      (node (ref "Q13") (pin "2") (pinfunction "E_2") (pintype "bidirectional"))
      (node (ref "R25") (pin "2") (pinfunction "2_2") (pintype "passive"))
      (node (ref "U$5") (pin "26-A12/MOSI1") (pinfunction "26-A12/MOSI1_26-A12/MOSI1") (pintype "bidirectional"))
    )
    (net (code "18") (name "A13") (class "Default")
      (node (ref "Q14") (pin "2") (pinfunction "E_2") (pintype "bidirectional"))
      (node (ref "R27") (pin "2") (pinfunction "2_2") (pintype "passive"))
      (node (ref "U$5") (pin "27-A13/SCK1") (pinfunction "27-A13/SCK1_27-A13/SCK1") (pintype "bidirectional"))
    )
    (net (code "19") (name "A14") (class "Default")
      (node (ref "Q15") (pin "2") (pinfunction "E_2") (pintype "bidirectional"))
      (node (ref "R29") (pin "2") (pinfunction "2_2") (pintype "passive"))
      (node (ref "U$5") (pin "38-A14/CS/IN1") (pinfunction "38-A14/CS/IN1_38-A14/CS/IN1") (pintype "bidirectional"))
    )
    (net (code "20") (name "A15") (class "Default")
      (node (ref "Q16") (pin "2") (pinfunction "E_2") (pintype "bidirectional"))
      (node (ref "R31") (pin "2") (pinfunction "2_2") (pintype "passive"))
      (node (ref "U$5") (pin "39-A15/CS/OUT1A") (pinfunction "39-A15/CS/OUT1A_39-A15/CS/OUT1A") (pintype "bidirectional"))
    )
    (net (code "21") (name "BVCC") (class "Default")
      (node (ref "C1") (pin "1") (pinfunction "1_1") (pintype "passive"))
      (node (ref "C12") (pin "1") (pinfunction "1_1") (pintype "passive"))
      (node (ref "C13") (pin "1") (pinfunction "1_1") (pintype "passive"))
      (node (ref "C16") (pin "1") (pinfunction "1_1") (pintype "passive"))
      (node (ref "C3") (pin "1") (pinfunction "1_1") (pintype "passive"))
      (node (ref "C6") (pin "1") (pinfunction "1_1") (pintype "passive"))
      (node (ref "C9") (pin "1") (pinfunction "1_1") (pintype "passive"))
      (node (ref "J1") (pin "1") (pinfunction "1_1") (pintype "passive"))
      (node (ref "PAD25") (pin "1") (pinfunction "P_1") (pintype "passive"))
      (node (ref "PAD26") (pin "1") (pinfunction "P_1") (pintype "passive"))
      (node (ref "Q17") (pin "1") (pinfunction "S_1_1") (pintype "bidirectional"))
      (node (ref "Q17") (pin "2") (pinfunction "S_2_2") (pintype "bidirectional"))
      (node (ref "Q17") (pin "3") (pinfunction "S_3_3") (pintype "bidirectional"))
      (node (ref "Q18") (pin "1") (pinfunction "S_1_1") (pintype "bidirectional"))
      (node (ref "Q18") (pin "2") (pinfunction "S_2_2") (pintype "bidirectional"))
      (node (ref "Q18") (pin "3") (pinfunction "S_3_3") (pintype "bidirectional"))
      (node (ref "Q19") (pin "1") (pinfunction "S_1_1") (pintype "bidirectional"))
      (node (ref "Q19") (pin "2") (pinfunction "S_2_2") (pintype "bidirectional"))
      (node (ref "Q19") (pin "3") (pinfunction "S_3_3") (pintype "bidirectional"))
      (node (ref "Q20") (pin "1") (pinfunction "S_1_1") (pintype "bidirectional"))
      (node (ref "Q20") (pin "2") (pinfunction "S_2_2") (pintype "bidirectional"))
      (node (ref "Q20") (pin "3") (pinfunction "S_3_3") (pintype "bidirectional"))
      (node (ref "U$6") (pin "12") (pinfunction "VBAT_12_12") (pintype "output"))
      (node (ref "U$7") (pin "12") (pinfunction "VBAT_12_12") (pintype "output"))
      (node (ref "U$8") (pin "12") (pinfunction "VBAT_12_12") (pintype "output"))
      (node (ref "U$9") (pin "12") (pinfunction "VBAT_12_12") (pintype "output"))
      (node (ref "U17") (pin "5") (pinfunction "VIN_5") (pintype "input"))
    )
    (net (code "22") (name "CP1") (class "Default")
      (node (ref "Q17") (pin "4") (pinfunction "G_4") (pintype "bidirectional"))
      (node (ref "U$6") (pin "11") (pinfunction "CP_11_11") (pintype "output"))
    )
    (net (code "23") (name "CP2") (class "Default")
      (node (ref "Q18") (pin "4") (pinfunction "G_4") (pintype "bidirectional"))
      (node (ref "U$7") (pin "11") (pinfunction "CP_11_11") (pintype "output"))
    )
    (net (code "24") (name "CP3") (class "Default")
      (node (ref "Q20") (pin "4") (pinfunction "G_4") (pintype "bidirectional"))
      (node (ref "U$8") (pin "11") (pinfunction "CP_11_11") (pintype "output"))
    )
    (net (code "25") (name "CP4") (class "Default")
      (node (ref "Q19") (pin "4") (pinfunction "G_4") (pintype "bidirectional"))
      (node (ref "U$9") (pin "11") (pinfunction "CP_11_11") (pintype "output"))
    )
    (net (code "26") (name "D2") (class "Default")
      (node (ref "PAD9") (pin "1") (pinfunction "P_1") (pintype "passive"))
      (node (ref "R33") (pin "2") (pinfunction "2_2") (pintype "passive"))
      (node (ref "R38") (pin "1") (pinfunction "1_1") (pintype "passive"))
      (node (ref "U$5") (pin "2-OUT2") (pinfunction "2-OUT2_2-OUT2") (pintype "bidirectional"))
    )
    (net (code "27") (name "D3") (class "Default")
      (node (ref "PAD10") (pin "1") (pinfunction "P_1") (pintype "passive"))
      (node (ref "R35") (pin "2") (pinfunction "2_2") (pintype "passive"))
      (node (ref "U$5") (pin "3-LRCLK2") (pinfunction "3-LRCLK2_3-LRCLK2") (pintype "bidirectional"))
    )
    (net (code "28") (name "D4") (class "Default")
      (node (ref "PAD11") (pin "1") (pinfunction "P_1") (pintype "passive"))
      (node (ref "R34") (pin "2") (pinfunction "2_2") (pintype "passive"))
      (node (ref "U$5") (pin "4-BCLK2") (pinfunction "4-BCLK2_4-BCLK2") (pintype "bidirectional"))
    )
    (net (code "29") (name "D5") (class "Default")
      (node (ref "PAD12") (pin "1") (pinfunction "P_1") (pintype "passive"))
      (node (ref "R39") (pin "2") (pinfunction "2_2") (pintype "passive"))
      (node (ref "R44") (pin "1") (pinfunction "1_1") (pintype "passive"))
      (node (ref "U$5") (pin "5-IN2") (pinfunction "5-IN2_5-IN2") (pintype "bidirectional"))
    )
    (net (code "30") (name "D6") (class "Default")
      (node (ref "PAD13") (pin "1") (pinfunction "P_1") (pintype "passive"))
      (node (ref "R41") (pin "2") (pinfunction "2_2") (pintype "passive"))
      (node (ref "U$5") (pin "6-OUT1D") (pinfunction "6-OUT1D_6-OUT1D") (pintype "bidirectional"))
    )
    (net (code "31") (name "D7") (class "Default")
      (node (ref "PAD14") (pin "1") (pinfunction "P_1") (pintype "passive"))
      (node (ref "R40") (pin "2") (pinfunction "2_2") (pintype "passive"))
      (node (ref "U$5") (pin "7-RX2/OUT1A") (pinfunction "7-RX2/OUT1A_7-RX2/OUT1A") (pintype "bidirectional"))
    )
    (net (code "32") (name "D8") (class "Default")
      (node (ref "PAD15") (pin "1") (pinfunction "P_1") (pintype "passive"))
      (node (ref "R45") (pin "2") (pinfunction "2_2") (pintype "passive"))
      (node (ref "R50") (pin "1") (pinfunction "1_1") (pintype "passive"))
      (node (ref "U$5") (pin "8-TX2/IN1") (pinfunction "8-TX2/IN1_8-TX2/IN1") (pintype "bidirectional"))
    )
    (net (code "33") (name "D9") (class "Default")
      (node (ref "PAD16") (pin "1") (pinfunction "P_1") (pintype "passive"))
      (node (ref "R47") (pin "2") (pinfunction "2_2") (pintype "passive"))
      (node (ref "U$5") (pin "9-OUT1C") (pinfunction "9-OUT1C_9-OUT1C") (pintype "bidirectional"))
    )
    (net (code "34") (name "D10") (class "Default")
      (node (ref "PAD17") (pin "1") (pinfunction "P_1") (pintype "passive"))
      (node (ref "R46") (pin "2") (pinfunction "2_2") (pintype "passive"))
      (node (ref "U$5") (pin "10-CS\\MQSR") (pinfunction "10-CS/MQSR_10-CS\\MQSR") (pintype "bidirectional"))
    )
    (net (code "35") (name "D28") (class "Default")
      (node (ref "PAD18") (pin "1") (pinfunction "P_1") (pintype "passive"))
      (node (ref "R51") (pin "2") (pinfunction "2_2") (pintype "passive"))
      (node (ref "R56") (pin "1") (pinfunction "1_1") (pintype "passive"))
      (node (ref "U$5") (pin "28-RX7") (pinfunction "28-RX7_28-RX7") (pintype "bidirectional"))
    )
    (net (code "36") (name "D29") (class "Default")
      (node (ref "PAD19") (pin "1") (pinfunction "P_1") (pintype "passive"))
      (node (ref "R53") (pin "2") (pinfunction "2_2") (pintype "passive"))
      (node (ref "U$5") (pin "29-TX7") (pinfunction "29-TX7_29-TX7") (pintype "bidirectional"))
    )
    (net (code "37") (name "D30") (class "Default")
      (node (ref "PAD20") (pin "1") (pinfunction "P_1") (pintype "passive"))
      (node (ref "R52") (pin "2") (pinfunction "2_2") (pintype "passive"))
      (node (ref "U$5") (pin "30-CRX3") (pinfunction "30-CRX3_30-CRX3") (pintype "bidirectional"))
    )
    (net (code "38") (name "FB") (class "Default")
      (node (ref "R57") (pin "1") (pinfunction "1_1") (pintype "passive"))
      (node (ref "R58") (pin "2") (pinfunction "2_2") (pintype "passive"))
      (node (ref "U17") (pin "2") (pinfunction "FB_2") (pintype "input"))
    )
    (net (code "39") (name "GND") (class "Default")
      (node (ref "C1") (pin "2") (pinfunction "2_2") (pintype "passive"))
      (node (ref "C10") (pin "2") (pinfunction "2_2") (pintype "passive"))
      (node (ref "C11") (pin "2") (pinfunction "2_2") (pintype "passive"))
      (node (ref "C12") (pin "2") (pinfunction "2_2") (pintype "passive"))
      (node (ref "C14") (pin "2") (pinfunction "2_2") (pintype "passive"))
      (node (ref "C15") (pin "2") (pinfunction "2_2") (pintype "passive"))
      (node (ref "C16") (pin "2") (pinfunction "2_2") (pintype "passive"))
      (node (ref "C17") (pin "2") (pinfunction "2_2") (pintype "passive"))
      (node (ref "C2") (pin "2") (pinfunction "2_2") (pintype "passive"))
      (node (ref "C3") (pin "2") (pinfunction "2_2") (pintype "passive"))
      (node (ref "C4") (pin "2") (pinfunction "2_2") (pintype "passive"))
      (node (ref "C5") (pin "2") (pinfunction "2_2") (pintype "passive"))
      (node (ref "C6") (pin "2") (pinfunction "2_2") (pintype "passive"))
      (node (ref "C7") (pin "2") (pinfunction "2_2") (pintype "passive"))
      (node (ref "C8") (pin "2") (pinfunction "2_2") (pintype "passive"))
      (node (ref "C9") (pin "2") (pinfunction "2_2") (pintype "passive"))
      (node (ref "D1") (pin "A") (pinfunction "A_A") (pintype "passive"))
      (node (ref "J1") (pin "2") (pinfunction "2_2") (pintype "passive"))
      (node (ref "JP2") (pin "1") (pinfunction "1_1") (pintype "passive"))
      (node (ref "JP2") (pin "3") (pinfunction "3_3") (pintype "passive"))
      (node (ref "PAD23") (pin "1") (pinfunction "P_1") (pintype "passive"))
      (node (ref "PAD24") (pin "1") (pinfunction "P_1") (pintype "passive"))
      (node (ref "PAD27") (pin "1") (pinfunction "P_1") (pintype "passive"))
      (node (ref "PAD28") (pin "1") (pinfunction "P_1") (pintype "passive"))
      (node (ref "R1") (pin "1") (pinfunction "1_1") (pintype "passive"))
      (node (ref "R10") (pin "1") (pinfunction "1_1") (pintype "passive"))
      (node (ref "R11") (pin "1") (pinfunction "1_1") (pintype "passive"))
      (node (ref "R12") (pin "1") (pinfunction "1_1") (pintype "passive"))
      (node (ref "R13") (pin "1") (pinfunction "1_1") (pintype "passive"))
      (node (ref "R14") (pin "1") (pinfunction "1_1") (pintype "passive"))
      (node (ref "R15") (pin "1") (pinfunction "1_1") (pintype "passive"))
      (node (ref "R16") (pin "1") (pinfunction "1_1") (pintype "passive"))
      (node (ref "R17") (pin "1") (pinfunction "1_1") (pintype "passive"))
      (node (ref "R18") (pin "1") (pinfunction "1_1") (pintype "passive"))
      (node (ref "R19") (pin "1") (pinfunction "1_1") (pintype "passive"))
      (node (ref "R2") (pin "1") (pinfunction "1_1") (pintype "passive"))
      (node (ref "R20") (pin "1") (pinfunction "1_1") (pintype "passive"))
      (node (ref "R21") (pin "1") (pinfunction "1_1") (pintype "passive"))
      (node (ref "R22") (pin "1") (pinfunction "1_1") (pintype "passive"))
      (node (ref "R23") (pin "1") (pinfunction "1_1") (pintype "passive"))
      (node (ref "R24") (pin "1") (pinfunction "1_1") (pintype "passive"))
      (node (ref "R25") (pin "1") (pinfunction "1_1") (pintype "passive"))
      (node (ref "R26") (pin "1") (pinfunction "1_1") (pintype "passive"))
      (node (ref "R27") (pin "1") (pinfunction "1_1") (pintype "passive"))
      (node (ref "R28") (pin "1") (pinfunction "1_1") (pintype "passive"))
      (node (ref "R29") (pin "1") (pinfunction "1_1") (pintype "passive"))
      (node (ref "R3") (pin "1") (pinfunction "1_1") (pintype "passive"))
      (node (ref "R30") (pin "1") (pinfunction "1_1") (pintype "passive"))
      (node (ref "R31") (pin "1") (pinfunction "1_1") (pintype "passive"))
      (node (ref "R32") (pin "1") (pinfunction "1_1") (pintype "passive"))
      (node (ref "R38") (pin "2") (pinfunction "2_2") (pintype "passive"))
      (node (ref "R4") (pin "1") (pinfunction "1_1") (pintype "passive"))
      (node (ref "R44") (pin "2") (pinfunction "2_2") (pintype "passive"))
      (node (ref "R5") (pin "1") (pinfunction "1_1") (pintype "passive"))
      (node (ref "R50") (pin "2") (pinfunction "2_2") (pintype "passive"))
      (node (ref "R56") (pin "2") (pinfunction "2_2") (pintype "passive"))
      (node (ref "R58") (pin "1") (pinfunction "1_1") (pintype "passive"))
      (node (ref "R6") (pin "1") (pinfunction "1_1") (pintype "passive"))
      (node (ref "R7") (pin "1") (pinfunction "1_1") (pintype "passive"))
      (node (ref "R8") (pin "1") (pinfunction "1_1") (pintype "passive"))
      (node (ref "R9") (pin "1") (pinfunction "1_1") (pintype "passive"))
      (node (ref "U$5") (pin "GND1") (pinfunction "GND1_GND1") (pintype "bidirectional"))
      (node (ref "U$5") (pin "GND3") (pinfunction "GND3_GND3") (pintype "bidirectional"))
      (node (ref "U$5") (pin "GND6") (pinfunction "GND6_GND6") (pintype "bidirectional"))
      (node (ref "U$6") (pin "18") (pinfunction "GNDB_18_18") (pintype "power_in"))
      (node (ref "U$6") (pin "19") (pinfunction "GNDB_19_19") (pintype "power_in"))
      (node (ref "U$6") (pin "20") (pinfunction "GNDB_20_20") (pintype "power_in"))
      (node (ref "U$6") (pin "26") (pinfunction "GNDA_26_26") (pintype "power_in"))
      (node (ref "U$6") (pin "27") (pinfunction "GNDA_27_27") (pintype "power_in"))
      (node (ref "U$6") (pin "28") (pinfunction "GNDA_28_28") (pintype "power_in"))
      (node (ref "U$7") (pin "18") (pinfunction "GNDB_18_18") (pintype "power_in"))
      (node (ref "U$7") (pin "19") (pinfunction "GNDB_19_19") (pintype "power_in"))
      (node (ref "U$7") (pin "20") (pinfunction "GNDB_20_20") (pintype "power_in"))
      (node (ref "U$7") (pin "26") (pinfunction "GNDA_26_26") (pintype "power_in"))
      (node (ref "U$7") (pin "27") (pinfunction "GNDA_27_27") (pintype "power_in"))
      (node (ref "U$7") (pin "28") (pinfunction "GNDA_28_28") (pintype "power_in"))
      (node (ref "U$8") (pin "18") (pinfunction "GNDB_18_18") (pintype "power_in"))
      (node (ref "U$8") (pin "19") (pinfunction "GNDB_19_19") (pintype "power_in"))
      (node (ref "U$8") (pin "20") (pinfunction "GNDB_20_20") (pintype "power_in"))
      (node (ref "U$8") (pin "26") (pinfunction "GNDA_26_26") (pintype "power_in"))
      (node (ref "U$8") (pin "27") (pinfunction "GNDA_27_27") (pintype "power_in"))
      (node (ref "U$8") (pin "28") (pinfunction "GNDA_28_28") (pintype "power_in"))
      (node (ref "U$9") (pin "18") (pinfunction "GNDB_18_18") (pintype "power_in"))
      (node (ref "U$9") (pin "19") (pinfunction "GNDB_19_19") (pintype "power_in"))
      (node (ref "U$9") (pin "20") (pinfunction "GNDB_20_20") (pintype "power_in"))
      (node (ref "U$9") (pin "26") (pinfunction "GNDA_26_26") (pintype "power_in"))
      (node (ref "U$9") (pin "27") (pinfunction "GNDA_27_27") (pintype "power_in"))
      (node (ref "U$9") (pin "28") (pinfunction "GNDA_28_28") (pintype "power_in"))
      (node (ref "U17") (pin "1") (pinfunction "GND_1") (pintype "power_in"))
    )
    (net (code "40") (name "M1A") (class "Default")
      (node (ref "PAD1") (pin "1") (pinfunction "P_1") (pintype "passive"))
      (node (ref "U$6") (pin "1") (pinfunction "OUTA_1_1") (pintype "output"))
      (node (ref "U$6") (pin "25") (pinfunction "OUTA_25_25") (pintype "output"))
      (node (ref "U$6") (pin "30") (pinfunction "OUTA_30_30") (pintype "output"))
      (node (ref "U$6") (pin "HS2") (pinfunction "OUTA_25_HS2") (pintype "output"))
    )
    (net (code "41") (name "M1B") (class "Default")
      (node (ref "PAD2") (pin "1") (pinfunction "P_1") (pintype "passive"))
      (node (ref "U$6") (pin "15") (pinfunction "OUTB_15_15") (pintype "output"))
      (node (ref "U$6") (pin "16") (pinfunction "OUTB_16_16") (pintype "output"))
      (node (ref "U$6") (pin "21") (pinfunction "OUTB_21_21") (pintype "output"))
      (node (ref "U$6") (pin "HS3") (pinfunction "OUTB_15_HS3") (pintype "output"))
    )
    (net (code "42") (name "M2A") (class "Default")
      (node (ref "PAD3") (pin "1") (pinfunction "P_1") (pintype "passive"))
      (node (ref "U$7") (pin "1") (pinfunction "OUTA_1_1") (pintype "output"))
      (node (ref "U$7") (pin "25") (pinfunction "OUTA_25_25") (pintype "output"))
      (node (ref "U$7") (pin "30") (pinfunction "OUTA_30_30") (pintype "output"))
      (node (ref "U$7") (pin "HS2") (pinfunction "OUTA_25_HS2") (pintype "output"))
    )
    (net (code "43") (name "M2B") (class "Default")
      (node (ref "PAD4") (pin "1") (pinfunction "P_1") (pintype "passive"))
      (node (ref "U$7") (pin "15") (pinfunction "OUTB_15_15") (pintype "output"))
      (node (ref "U$7") (pin "16") (pinfunction "OUTB_16_16") (pintype "output"))
      (node (ref "U$7") (pin "21") (pinfunction "OUTB_21_21") (pintype "output"))
      (node (ref "U$7") (pin "HS3") (pinfunction "OUTB_15_HS3") (pintype "output"))
    )
    (net (code "44") (name "M3A") (class "Default")
      (node (ref "PAD5") (pin "1") (pinfunction "P_1") (pintype "passive"))
      (node (ref "U$8") (pin "1") (pinfunction "OUTA_1_1") (pintype "output"))
      (node (ref "U$8") (pin "25") (pinfunction "OUTA_25_25") (pintype "output"))
      (node (ref "U$8") (pin "30") (pinfunction "OUTA_30_30") (pintype "output"))
      (node (ref "U$8") (pin "HS2") (pinfunction "OUTA_25_HS2") (pintype "output"))
    )
    (net (code "45") (name "M3B") (class "Default")
      (node (ref "PAD6") (pin "1") (pinfunction "P_1") (pintype "passive"))
      (node (ref "U$8") (pin "15") (pinfunction "OUTB_15_15") (pintype "output"))
      (node (ref "U$8") (pin "16") (pinfunction "OUTB_16_16") (pintype "output"))
      (node (ref "U$8") (pin "21") (pinfunction "OUTB_21_21") (pintype "output"))
      (node (ref "U$8") (pin "HS3") (pinfunction "OUTB_15_HS3") (pintype "output"))
    )
    (net (code "46") (name "M4A") (class "Default")
      (node (ref "PAD7") (pin "1") (pinfunction "P_1") (pintype "passive"))
      (node (ref "U$9") (pin "1") (pinfunction "OUTA_1_1") (pintype "output"))
      (node (ref "U$9") (pin "25") (pinfunction "OUTA_25_25") (pintype "output"))
      (node (ref "U$9") (pin "30") (pinfunction "OUTA_30_30") (pintype "output"))
      (node (ref "U$9") (pin "HS2") (pinfunction "OUTA_25_HS2") (pintype "output"))
    )
    (net (code "47") (name "M4B") (class "Default")
      (node (ref "PAD8") (pin "1") (pinfunction "P_1") (pintype "passive"))
      (node (ref "U$9") (pin "15") (pinfunction "OUTB_15_15") (pintype "output"))
      (node (ref "U$9") (pin "16") (pinfunction "OUTB_16_16") (pintype "output"))
      (node (ref "U$9") (pin "21") (pinfunction "OUTB_21_21") (pintype "output"))
      (node (ref "U$9") (pin "HS3") (pinfunction "OUTB_15_HS3") (pintype "output"))
    )
    (net (code "48") (name "Net-(D1-K)") (class "Default")
      (node (ref "D1") (pin "C") (pinfunction "K_C") (pintype "passive"))
      (node (ref "L1") (pin "1") (pinfunction "1_1") (pintype "bidirectional"))
      (node (ref "U17") (pin "3") (pinfunction "SW_3") (pintype "output"))
      (node (ref "U17") (pin "3.1") (pinfunction "SW_3.1") (pintype "output"))
    )
    (net (code "49") (name "Net-(LED1-K)") (class "Default")
      (node (ref "LED1") (pin "2") (pinfunction "K_2") (pintype "bidirectional"))
      (node (ref "R2") (pin "2") (pinfunction "2_2") (pintype "passive"))
    )
    (net (code "50") (name "Net-(LED2-K)") (class "Default")
      (node (ref "LED2") (pin "2") (pinfunction "K_2") (pintype "bidirectional"))
      (node (ref "R4") (pin "2") (pinfunction "2_2") (pintype "passive"))
    )
    (net (code "51") (name "Net-(LED3-K)") (class "Default")
      (node (ref "LED3") (pin "2") (pinfunction "K_2") (pintype "bidirectional"))
      (node (ref "R6") (pin "2") (pinfunction "2_2") (pintype "passive"))
    )
    (net (code "52") (name "Net-(LED4-K)") (class "Default")
      (node (ref "LED4") (pin "2") (pinfunction "K_2") (pintype "bidirectional"))
      (node (ref "R8") (pin "2") (pinfunction "2_2") (pintype "passive"))
    )
    (net (code "53") (name "Net-(LED5-K)") (class "Default")
      (node (ref "LED5") (pin "2") (pinfunction "K_2") (pintype "bidirectional"))
      (node (ref "R10") (pin "2") (pinfunction "2_2") (pintype "passive"))
    )
    (net (code "54") (name "Net-(LED6-K)") (class "Default")
      (node (ref "LED6") (pin "2") (pinfunction "K_2") (pintype "bidirectional"))
      (node (ref "R12") (pin "2") (pinfunction "2_2") (pintype "passive"))
    )
    (net (code "55") (name "Net-(LED7-K)") (class "Default")
      (node (ref "LED7") (pin "2") (pinfunction "K_2") (pintype "bidirectional"))
      (node (ref "R14") (pin "2") (pinfunction "2_2") (pintype "passive"))
    )
    (net (code "56") (name "Net-(LED8-K)") (class "Default")
      (node (ref "LED8") (pin "2") (pinfunction "K_2") (pintype "bidirectional"))
      (node (ref "R16") (pin "2") (pinfunction "2_2") (pintype "passive"))
    )
    (net (code "57") (name "Net-(LED9-K)") (class "Default")
      (node (ref "LED9") (pin "2") (pinfunction "K_2") (pintype "bidirectional"))
      (node (ref "R18") (pin "2") (pinfunction "2_2") (pintype "passive"))
    )
    (net (code "58") (name "Net-(LED10-K)") (class "Default")
      (node (ref "LED10") (pin "2") (pinfunction "K_2") (pintype "bidirectional"))
      (node (ref "R20") (pin "2") (pinfunction "2_2") (pintype "passive"))
    )
    (net (code "59") (name "Net-(LED11-K)") (class "Default")
      (node (ref "LED11") (pin "2") (pinfunction "K_2") (pintype "bidirectional"))
      (node (ref "R22") (pin "2") (pinfunction "2_2") (pintype "passive"))
    )
    (net (code "60") (name "Net-(LED12-K)") (class "Default")
      (node (ref "LED12") (pin "2") (pinfunction "K_2") (pintype "bidirectional"))
      (node (ref "R24") (pin "2") (pinfunction "2_2") (pintype "passive"))
    )
    (net (code "61") (name "Net-(LED13-K)") (class "Default")
      (node (ref "LED13") (pin "2") (pinfunction "K_2") (pintype "bidirectional"))
      (node (ref "R26") (pin "2") (pinfunction "2_2") (pintype "passive"))
    )
    (net (code "62") (name "Net-(LED14-K)") (class "Default")
      (node (ref "LED14") (pin "2") (pinfunction "K_2") (pintype "bidirectional"))
      (node (ref "R28") (pin "2") (pinfunction "2_2") (pintype "passive"))
    )
    (net (code "63") (name "Net-(LED15-K)") (class "Default")
      (node (ref "LED15") (pin "2") (pinfunction "K_2") (pintype "bidirectional"))
      (node (ref "R30") (pin "2") (pinfunction "2_2") (pintype "passive"))
    )
    (net (code "64") (name "Net-(LED16-K)") (class "Default")
      (node (ref "LED16") (pin "2") (pinfunction "K_2") (pintype "bidirectional"))
      (node (ref "R32") (pin "2") (pinfunction "2_2") (pintype "passive"))
    )
    (net (code "65") (name "Net-(U$6-ENA{slash}DIAGA_5)") (class "Default")
      (node (ref "R36") (pin "1") (pinfunction "1_1") (pintype "passive"))
      (node (ref "U$6") (pin "5") (pinfunction "ENA/DIAGA_5_5") (pintype "output"))
    )
    (net (code "66") (name "Net-(U$6-ENB{slash}DIAGB_9)") (class "Default")
      (node (ref "R37") (pin "1") (pinfunction "1_1") (pintype "passive"))
      (node (ref "U$6") (pin "9") (pinfunction "ENB/DIAGB_9_9") (pintype "output"))
    )
    (net (code "67") (name "Net-(U$6-INA_4)") (class "Default")
      (node (ref "R34") (pin "1") (pinfunction "1_1") (pintype "passive"))
      (node (ref "U$6") (pin "4") (pinfunction "INA_4_4") (pintype "input"))
    )
    (net (code "68") (name "Net-(U$6-INB_10)") (class "Default")
      (node (ref "R35") (pin "1") (pinfunction "1_1") (pintype "passive"))
      (node (ref "U$6") (pin "10") (pinfunction "INB_10_10") (pintype "input"))
    )
    (net (code "69") (name "Net-(U$6-PWM_7)") (class "Default")
      (node (ref "R33") (pin "1") (pinfunction "1_1") (pintype "passive"))
      (node (ref "U$6") (pin "7") (pinfunction "PWM_7_7") (pintype "input"))
    )
    (net (code "70") (name "Net-(U$7-ENA{slash}DIAGA_5)") (class "Default")
      (node (ref "R42") (pin "1") (pinfunction "1_1") (pintype "passive"))
      (node (ref "U$7") (pin "5") (pinfunction "ENA/DIAGA_5_5") (pintype "output"))
    )
    (net (code "71") (name "Net-(U$7-ENB{slash}DIAGB_9)") (class "Default")
      (node (ref "R43") (pin "1") (pinfunction "1_1") (pintype "passive"))
      (node (ref "U$7") (pin "9") (pinfunction "ENB/DIAGB_9_9") (pintype "output"))
    )
    (net (code "72") (name "Net-(U$7-INA_4)") (class "Default")
      (node (ref "R40") (pin "1") (pinfunction "1_1") (pintype "passive"))
      (node (ref "U$7") (pin "4") (pinfunction "INA_4_4") (pintype "input"))
    )
    (net (code "73") (name "Net-(U$7-INB_10)") (class "Default")
      (node (ref "R41") (pin "1") (pinfunction "1_1") (pintype "passive"))
      (node (ref "U$7") (pin "10") (pinfunction "INB_10_10") (pintype "input"))
    )
    (net (code "74") (name "Net-(U$7-PWM_7)") (class "Default")
      (node (ref "R39") (pin "1") (pinfunction "1_1") (pintype "passive"))
      (node (ref "U$7") (pin "7") (pinfunction "PWM_7_7") (pintype "input"))
    )
    (net (code "75") (name "Net-(U$8-ENA{slash}DIAGA_5)") (class "Default")
      (node (ref "R48") (pin "1") (pinfunction "1_1") (pintype "passive"))
      (node (ref "U$8") (pin "5") (pinfunction "ENA/DIAGA_5_5") (pintype "output"))
    )
    (net (code "76") (name "Net-(U$8-ENB{slash}DIAGB_9)") (class "Default")
      (node (ref "R49") (pin "1") (pinfunction "1_1") (pintype "passive"))
      (node (ref "U$8") (pin "9") (pinfunction "ENB/DIAGB_9_9") (pintype "output"))
    )
    (net (code "77") (name "Net-(U$8-INA_4)") (class "Default")
      (node (ref "R46") (pin "1") (pinfunction "1_1") (pintype "passive"))
      (node (ref "U$8") (pin "4") (pinfunction "INA_4_4") (pintype "input"))
    )
    (net (code "78") (name "Net-(U$8-INB_10)") (class "Default")
      (node (ref "R47") (pin "1") (pinfunction "1_1") (pintype "passive"))
      (node (ref "U$8") (pin "10") (pinfunction "INB_10_10") (pintype "input"))
    )
    (net (code "79") (name "Net-(U$8-PWM_7)") (class "Default")
      (node (ref "R45") (pin "1") (pinfunction "1_1") (pintype "passive"))
      (node (ref "U$8") (pin "7") (pinfunction "PWM_7_7") (pintype "input"))
    )
    (net (code "80") (name "Net-(U$9-ENA{slash}DIAGA_5)") (class "Default")
      (node (ref "R54") (pin "1") (pinfunction "1_1") (pintype "passive"))
      (node (ref "U$9") (pin "5") (pinfunction "ENA/DIAGA_5_5") (pintype "output"))
    )
    (net (code "81") (name "Net-(U$9-ENB{slash}DIAGB_9)") (class "Default")
      (node (ref "R55") (pin "1") (pinfunction "1_1") (pintype "passive"))
      (node (ref "U$9") (pin "9") (pinfunction "ENB/DIAGB_9_9") (pintype "output"))
    )
    (net (code "82") (name "Net-(U$9-INA_4)") (class "Default")
      (node (ref "R52") (pin "1") (pinfunction "1_1") (pintype "passive"))
      (node (ref "U$9") (pin "4") (pinfunction "INA_4_4") (pintype "input"))
    )
    (net (code "83") (name "Net-(U$9-INB_10)") (class "Default")
      (node (ref "R53") (pin "1") (pinfunction "1_1") (pintype "passive"))
      (node (ref "U$9") (pin "10") (pinfunction "INB_10_10") (pintype "input"))
    )
    (net (code "84") (name "Net-(U$9-PWM_7)") (class "Default")
      (node (ref "R51") (pin "1") (pinfunction "1_1") (pintype "passive"))
      (node (ref "U$9") (pin "7") (pinfunction "PWM_7_7") (pintype "input"))
    )
    (net (code "85") (name "Net-(U17-VC)") (class "Default")
      (node (ref "C13") (pin "2") (pinfunction "2_2") (pintype "passive"))
      (node (ref "U17") (pin "4") (pinfunction "VC_4") (pintype "passive"))
    )
    (net (code "86") (name "VOUT1") (class "Default")
      (node (ref "C2") (pin "1") (pinfunction "1_1") (pintype "passive"))
      (node (ref "C4") (pin "1") (pinfunction "1_1") (pintype "passive"))
      (node (ref "Q17") (pin "5") (pinfunction "D_1_5") (pintype "bidirectional"))
      (node (ref "Q17") (pin "6") (pinfunction "D_2_6") (pintype "bidirectional"))
      (node (ref "Q17") (pin "7") (pinfunction "D_3_7") (pintype "bidirectional"))
      (node (ref "Q17") (pin "8") (pinfunction "D_4_8") (pintype "bidirectional"))
      (node (ref "Q17") (pin "9") (pinfunction "EP_9") (pintype "bidirectional"))
      (node (ref "U$6") (pin "13") (pinfunction "VCC_13_13") (pintype "power_in"))
      (node (ref "U$6") (pin "23") (pinfunction "VCC_23_23") (pintype "power_in"))
      (node (ref "U$6") (pin "3") (pinfunction "VCC_3_3") (pintype "power_in"))
      (node (ref "U$6") (pin "HS1") (pinfunction "VCC_3_HS1") (pintype "power_in"))
    )
    (net (code "87") (name "VOUT2") (class "Default")
      (node (ref "C17") (pin "1") (pinfunction "1_1") (pintype "passive"))
      (node (ref "C5") (pin "1") (pinfunction "1_1") (pintype "passive"))
      (node (ref "Q18") (pin "5") (pinfunction "D_1_5") (pintype "bidirectional"))
      (node (ref "Q18") (pin "6") (pinfunction "D_2_6") (pintype "bidirectional"))
      (node (ref "Q18") (pin "7") (pinfunction "D_3_7") (pintype "bidirectional"))
      (node (ref "Q18") (pin "8") (pinfunction "D_4_8") (pintype "bidirectional"))
      (node (ref "Q18") (pin "9") (pinfunction "EP_9") (pintype "bidirectional"))
      (node (ref "U$7") (pin "13") (pinfunction "VCC_13_13") (pintype "power_in"))
      (node (ref "U$7") (pin "23") (pinfunction "VCC_23_23") (pintype "power_in"))
      (node (ref "U$7") (pin "3") (pinfunction "VCC_3_3") (pintype "power_in"))
      (node (ref "U$7") (pin "HS1") (pinfunction "VCC_3_HS1") (pintype "power_in"))
    )
    (net (code "88") (name "VOUT3") (class "Default")
      (node (ref "C7") (pin "1") (pinfunction "1_1") (pintype "passive"))
      (node (ref "C8") (pin "1") (pinfunction "1_1") (pintype "passive"))
      (node (ref "Q20") (pin "5") (pinfunction "D_1_5") (pintype "bidirectional"))
      (node (ref "Q20") (pin "6") (pinfunction "D_2_6") (pintype "bidirectional"))
      (node (ref "Q20") (pin "7") (pinfunction "D_3_7") (pintype "bidirectional"))
      (node (ref "Q20") (pin "8") (pinfunction "D_4_8") (pintype "bidirectional"))
      (node (ref "Q20") (pin "9") (pinfunction "EP_9") (pintype "bidirectional"))
      (node (ref "U$8") (pin "13") (pinfunction "VCC_13_13") (pintype "power_in"))
      (node (ref "U$8") (pin "23") (pinfunction "VCC_23_23") (pintype "power_in"))
      (node (ref "U$8") (pin "3") (pinfunction "VCC_3_3") (pintype "power_in"))
      (node (ref "U$8") (pin "HS1") (pinfunction "VCC_3_HS1") (pintype "power_in"))
    )
    (net (code "89") (name "VOUT4") (class "Default")
      (node (ref "C10") (pin "1") (pinfunction "1_1") (pintype "passive"))
      (node (ref "C11") (pin "1") (pinfunction "1_1") (pintype "passive"))
      (node (ref "Q19") (pin "5") (pinfunction "D_1_5") (pintype "bidirectional"))
      (node (ref "Q19") (pin "6") (pinfunction "D_2_6") (pintype "bidirectional"))
      (node (ref "Q19") (pin "7") (pinfunction "D_3_7") (pintype "bidirectional"))
      (node (ref "Q19") (pin "8") (pinfunction "D_4_8") (pintype "bidirectional"))
      (node (ref "Q19") (pin "9") (pinfunction "EP_9") (pintype "bidirectional"))
      (node (ref "U$9") (pin "13") (pinfunction "VCC_13_13") (pintype "power_in"))
      (node (ref "U$9") (pin "23") (pinfunction "VCC_23_23") (pintype "power_in"))
      (node (ref "U$9") (pin "3") (pinfunction "VCC_3_3") (pintype "power_in"))
      (node (ref "U$9") (pin "HS1") (pinfunction "VCC_3_HS1") (pintype "power_in"))
    )
    (net (code "90") (name "unconnected-(U$5-5V-Pad+5V)") (class "Default")
      (node (ref "U$5") (pin "+5V") (pinfunction "5V_+5V") (pintype "bidirectional"))
    )
    (net (code "91") (name "unconnected-(U$5-35{slash}TX8-Pad35-TX8)") (class "Default")
      (node (ref "U$5") (pin "35-TX8") (pinfunction "35/TX8_35-TX8") (pintype "bidirectional"))
    )
    (net (code "92") (name "unconnected-(U$5-Pad3V3-2)") (class "Default")
      (node (ref "U$5") (pin "3V3-2") (pinfunction "3V3-2_3V3-2") (pintype "bidirectional"))
    )
    (net (code "93") (name "unconnected-(U$5-Pad11-MOSI{slash}CTX1)") (class "Default")
      (node (ref "U$5") (pin "11-MOSI/CTX1") (pinfunction "11-MOSI/CTX1_11-MOSI/CTX1") (pintype "bidirectional"))
    )
    (net (code "94") (name "unconnected-(U$5-Pad12-MISO{slash}MQSL)") (class "Default")
      (node (ref "U$5") (pin "12-MISO/MQSL") (pinfunction "12-MISO/MQSL_12-MISO/MQSL") (pintype "bidirectional"))
    )
    (net (code "95") (name "unconnected-(U$5-Pad13-SCK{slash}LED)") (class "Default")
      (node (ref "U$5") (pin "13-SCK/LED") (pinfunction "13-SCK/LED_13-SCK/LED") (pintype "bidirectional"))
    )
    (net (code "96") (name "unconnected-(U$5-Pad31-CTX3)") (class "Default")
      (node (ref "U$5") (pin "31-CTX3") (pinfunction "31-CTX3_31-CTX3") (pintype "bidirectional"))
    )
    (net (code "97") (name "unconnected-(U$5-Pad32-OUT1B)") (class "Default")
      (node (ref "U$5") (pin "32-OUT1B") (pinfunction "32-OUT1B_32-OUT1B") (pintype "bidirectional"))
    )
    (net (code "98") (name "unconnected-(U$5-Pad33-MCLK2)") (class "Default")
      (node (ref "U$5") (pin "33-MCLK2") (pinfunction "33-MCLK2_33-MCLK2") (pintype "bidirectional"))
    )
    (net (code "99") (name "unconnected-(U$5-Pad34-RX8)") (class "Default")
      (node (ref "U$5") (pin "34-RX8") (pinfunction "34-RX8_34-RX8") (pintype "bidirectional"))
    )
    (net (code "100") (name "unconnected-(U$5-Pad36-PWM)") (class "Default")
      (node (ref "U$5") (pin "36-PWM") (pinfunction "36-PWM_36-PWM") (pintype "bidirectional"))
    )
    (net (code "101") (name "unconnected-(U$5-Pad37-PWM)") (class "Default")
      (node (ref "U$5") (pin "37-PWM") (pinfunction "37-PWM_37-PWM") (pintype "bidirectional"))
    )
    (net (code "102") (name "unconnected-(U$5-Pad40-A16{slash}CS1)") (class "Default")
      (node (ref "U$5") (pin "40-A16/CS1") (pinfunction "40-A16/CS1_40-A16/CS1") (pintype "bidirectional"))
    )
    (net (code "103") (name "unconnected-(U$5-Pad41-A17{slash}MISO1)") (class "Default")
      (node (ref "U$5") (pin "41-A17/MISO1") (pinfunction "41-A17/MISO1_41-A17/MISO1") (pintype "bidirectional"))
    )
    (net (code "104") (name "unconnected-(U$5-PadDM)") (class "Default")
      (node (ref "U$5") (pin "DM") (pinfunction "DM_DM") (pintype "bidirectional"))
    )
    (net (code "105") (name "unconnected-(U$5-PadDP)") (class "Default")
      (node (ref "U$5") (pin "DP") (pinfunction "DP_DP") (pintype "bidirectional"))
    )
    (net (code "106") (name "unconnected-(U$5-PadGND2)") (class "Default")
      (node (ref "U$5") (pin "GND2") (pinfunction "GND2_GND2") (pintype "bidirectional"))
    )
    (net (code "107") (name "unconnected-(U$5-PadGND4)") (class "Default")
      (node (ref "U$5") (pin "GND4") (pinfunction "GND4_GND4") (pintype "bidirectional"))
    )
    (net (code "108") (name "unconnected-(U$5-PadGND5)") (class "Default")
      (node (ref "U$5") (pin "GND5") (pinfunction "GND5_GND5") (pintype "bidirectional"))
    )
    (net (code "109") (name "unconnected-(U$5-PadON{slash}OFF)") (class "Default")
      (node (ref "U$5") (pin "ON/OFF") (pinfunction "ON/OFF_ON/OFF") (pintype "bidirectional"))
    )
    (net (code "110") (name "unconnected-(U$5-PadPROGRAM)") (class "Default")
      (node (ref "U$5") (pin "PROGRAM") (pinfunction "PROGRAM_PROGRAM") (pintype "bidirectional"))
    )
    (net (code "111") (name "unconnected-(U$5-PadVBAT)") (class "Default")
      (node (ref "U$5") (pin "VBAT") (pinfunction "VBAT_VBAT") (pintype "bidirectional"))
    )
    (net (code "112") (name "unconnected-(U$5-PadVUSB)") (class "Default")
      (node (ref "U$5") (pin "VUSB") (pinfunction "VUSB_VUSB") (pintype "bidirectional"))
    )
    (net (code "113") (name "unconnected-(U$6-CS_8-Pad8)") (class "Default")
      (node (ref "U$6") (pin "8") (pinfunction "CS_8_8") (pintype "output"))
    )
    (net (code "114") (name "unconnected-(U$6-CS_DIS_6-Pad6)") (class "Default")
      (node (ref "U$6") (pin "6") (pinfunction "CS_DIS_6_6") (pintype "input"))
    )
    (net (code "115") (name "unconnected-(U$6-N.C._2-Pad2)") (class "Default")
      (node (ref "U$6") (pin "2") (pinfunction "N.C._2_2") (pintype "no_connect"))
    )
    (net (code "116") (name "unconnected-(U$6-N.C._29-Pad29)") (class "Default")
      (node (ref "U$6") (pin "29") (pinfunction "N.C._29_29") (pintype "no_connect"))
    )
    (net (code "117") (name "unconnected-(U$6-NC_14-Pad14)") (class "Default")
      (node (ref "U$6") (pin "14") (pinfunction "NC_14_14") (pintype "no_connect"))
    )
    (net (code "118") (name "unconnected-(U$6-NC_17-Pad17)") (class "Default")
      (node (ref "U$6") (pin "17") (pinfunction "NC_17_17") (pintype "no_connect"))
    )
    (net (code "119") (name "unconnected-(U$6-NC_22-Pad22)") (class "Default")
      (node (ref "U$6") (pin "22") (pinfunction "NC_22_22") (pintype "no_connect"))
    )
    (net (code "120") (name "unconnected-(U$6-NC_24-Pad24)") (class "Default")
      (node (ref "U$6") (pin "24") (pinfunction "NC_24_24") (pintype "no_connect"))
    )
    (net (code "121") (name "unconnected-(U$7-CS_8-Pad8)") (class "Default")
      (node (ref "U$7") (pin "8") (pinfunction "CS_8_8") (pintype "output"))
    )
    (net (code "122") (name "unconnected-(U$7-CS_DIS_6-Pad6)") (class "Default")
      (node (ref "U$7") (pin "6") (pinfunction "CS_DIS_6_6") (pintype "input"))
    )
    (net (code "123") (name "unconnected-(U$7-N.C._2-Pad2)") (class "Default")
      (node (ref "U$7") (pin "2") (pinfunction "N.C._2_2") (pintype "no_connect"))
    )
    (net (code "124") (name "unconnected-(U$7-N.C._29-Pad29)") (class "Default")
      (node (ref "U$7") (pin "29") (pinfunction "N.C._29_29") (pintype "no_connect"))
    )
    (net (code "125") (name "unconnected-(U$7-NC_14-Pad14)") (class "Default")
      (node (ref "U$7") (pin "14") (pinfunction "NC_14_14") (pintype "no_connect"))
    )
    (net (code "126") (name "unconnected-(U$7-NC_17-Pad17)") (class "Default")
      (node (ref "U$7") (pin "17") (pinfunction "NC_17_17") (pintype "no_connect"))
    )
    (net (code "127") (name "unconnected-(U$7-NC_22-Pad22)") (class "Default")
      (node (ref "U$7") (pin "22") (pinfunction "NC_22_22") (pintype "no_connect"))
    )
    (net (code "128") (name "unconnected-(U$7-NC_24-Pad24)") (class "Default")
      (node (ref "U$7") (pin "24") (pinfunction "NC_24_24") (pintype "no_connect"))
    )
    (net (code "129") (name "unconnected-(U$8-CS_8-Pad8)") (class "Default")
      (node (ref "U$8") (pin "8") (pinfunction "CS_8_8") (pintype "output"))
    )
    (net (code "130") (name "unconnected-(U$8-CS_DIS_6-Pad6)") (class "Default")
      (node (ref "U$8") (pin "6") (pinfunction "CS_DIS_6_6") (pintype "input"))
    )
    (net (code "131") (name "unconnected-(U$8-N.C._2-Pad2)") (class "Default")
      (node (ref "U$8") (pin "2") (pinfunction "N.C._2_2") (pintype "no_connect"))
    )
    (net (code "132") (name "unconnected-(U$8-N.C._29-Pad29)") (class "Default")
      (node (ref "U$8") (pin "29") (pinfunction "N.C._29_29") (pintype "no_connect"))
    )
    (net (code "133") (name "unconnected-(U$8-NC_14-Pad14)") (class "Default")
      (node (ref "U$8") (pin "14") (pinfunction "NC_14_14") (pintype "no_connect"))
    )
    (net (code "134") (name "unconnected-(U$8-NC_17-Pad17)") (class "Default")
      (node (ref "U$8") (pin "17") (pinfunction "NC_17_17") (pintype "no_connect"))
    )
    (net (code "135") (name "unconnected-(U$8-NC_22-Pad22)") (class "Default")
      (node (ref "U$8") (pin "22") (pinfunction "NC_22_22") (pintype "no_connect"))
    )
    (net (code "136") (name "unconnected-(U$8-NC_24-Pad24)") (class "Default")
      (node (ref "U$8") (pin "24") (pinfunction "NC_24_24") (pintype "no_connect"))
    )
    (net (code "137") (name "unconnected-(U$9-CS_8-Pad8)") (class "Default")
      (node (ref "U$9") (pin "8") (pinfunction "CS_8_8") (pintype "output"))
    )
    (net (code "138") (name "unconnected-(U$9-CS_DIS_6-Pad6)") (class "Default")
      (node (ref "U$9") (pin "6") (pinfunction "CS_DIS_6_6") (pintype "input"))
    )
    (net (code "139") (name "unconnected-(U$9-N.C._2-Pad2)") (class "Default")
      (node (ref "U$9") (pin "2") (pinfunction "N.C._2_2") (pintype "no_connect"))
    )
    (net (code "140") (name "unconnected-(U$9-N.C._29-Pad29)") (class "Default")
      (node (ref "U$9") (pin "29") (pinfunction "N.C._29_29") (pintype "no_connect"))
    )
    (net (code "141") (name "unconnected-(U$9-NC_14-Pad14)") (class "Default")
      (node (ref "U$9") (pin "14") (pinfunction "NC_14_14") (pintype "no_connect"))
    )
    (net (code "142") (name "unconnected-(U$9-NC_17-Pad17)") (class "Default")
      (node (ref "U$9") (pin "17") (pinfunction "NC_17_17") (pintype "no_connect"))
    )
    (net (code "143") (name "unconnected-(U$9-NC_22-Pad22)") (class "Default")
      (node (ref "U$9") (pin "22") (pinfunction "NC_22_22") (pintype "no_connect"))
    )
    (net (code "144") (name "unconnected-(U$9-NC_24-Pad24)") (class "Default")
      (node (ref "U$9") (pin "24") (pinfunction "NC_24_24") (pintype "no_connect"))
    )
  )
)
